# untitled.net
KiCad netlist of a schematic drawn in EAGLE
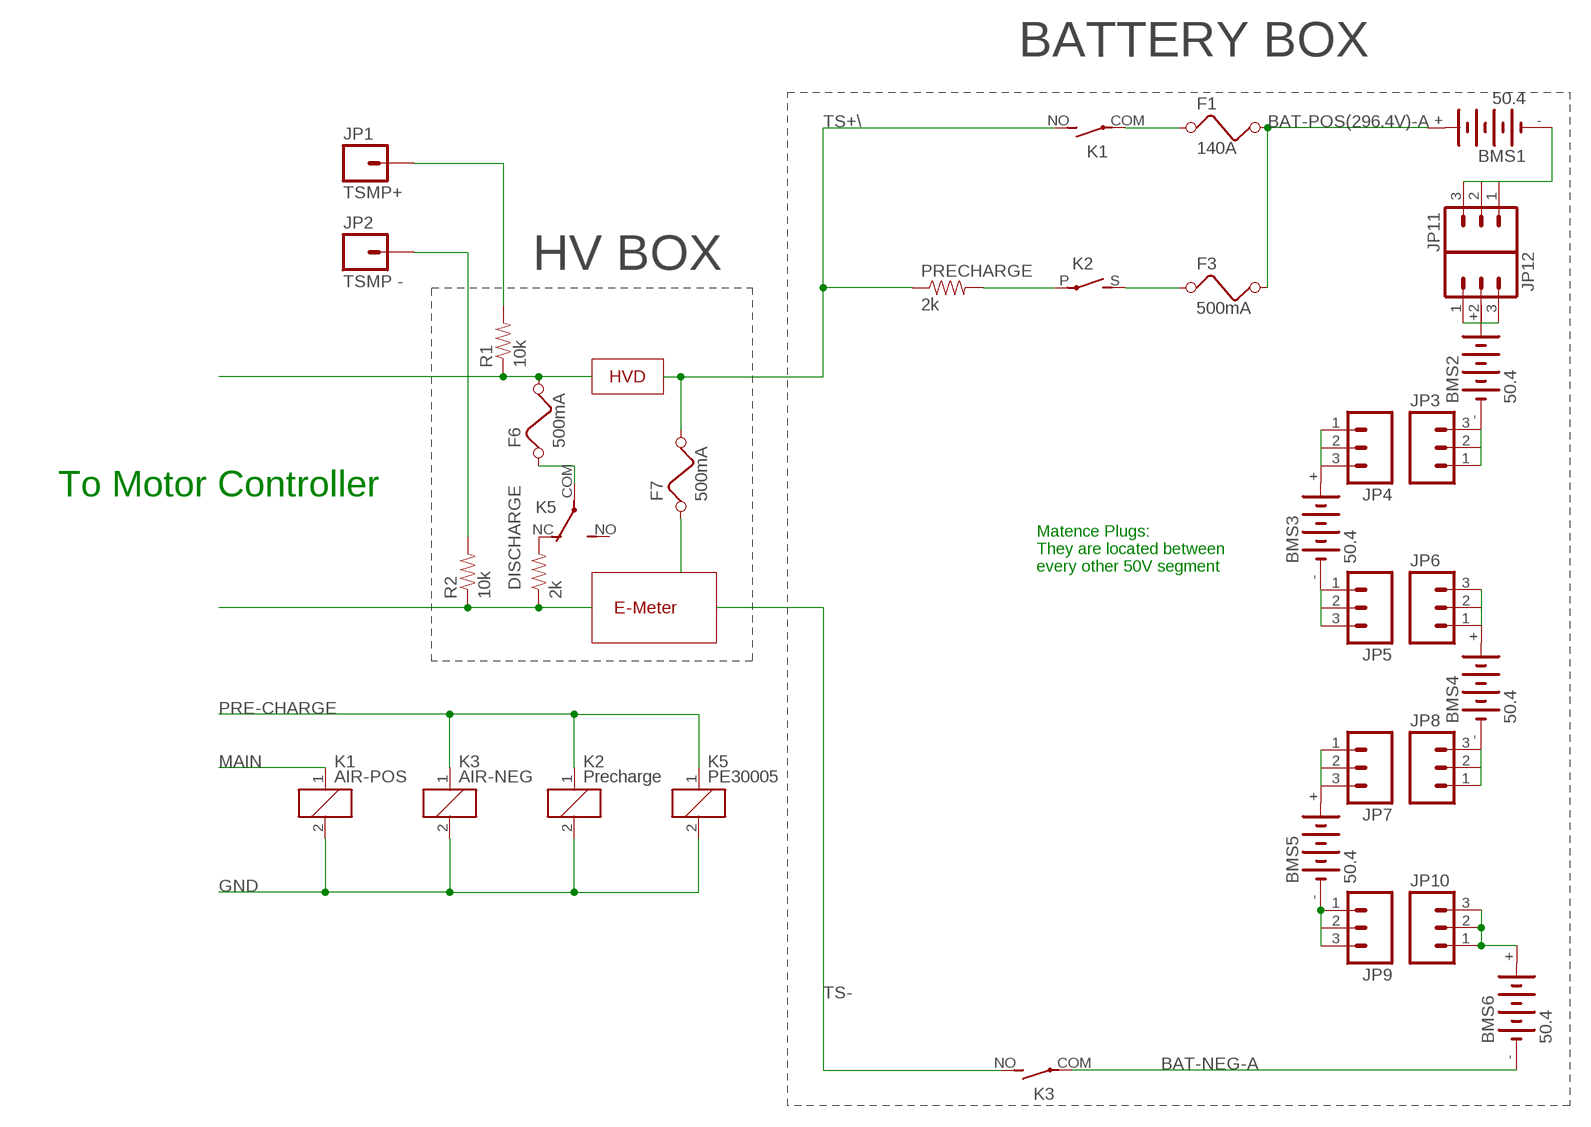
[diagram p0: schematic, sheet 1]
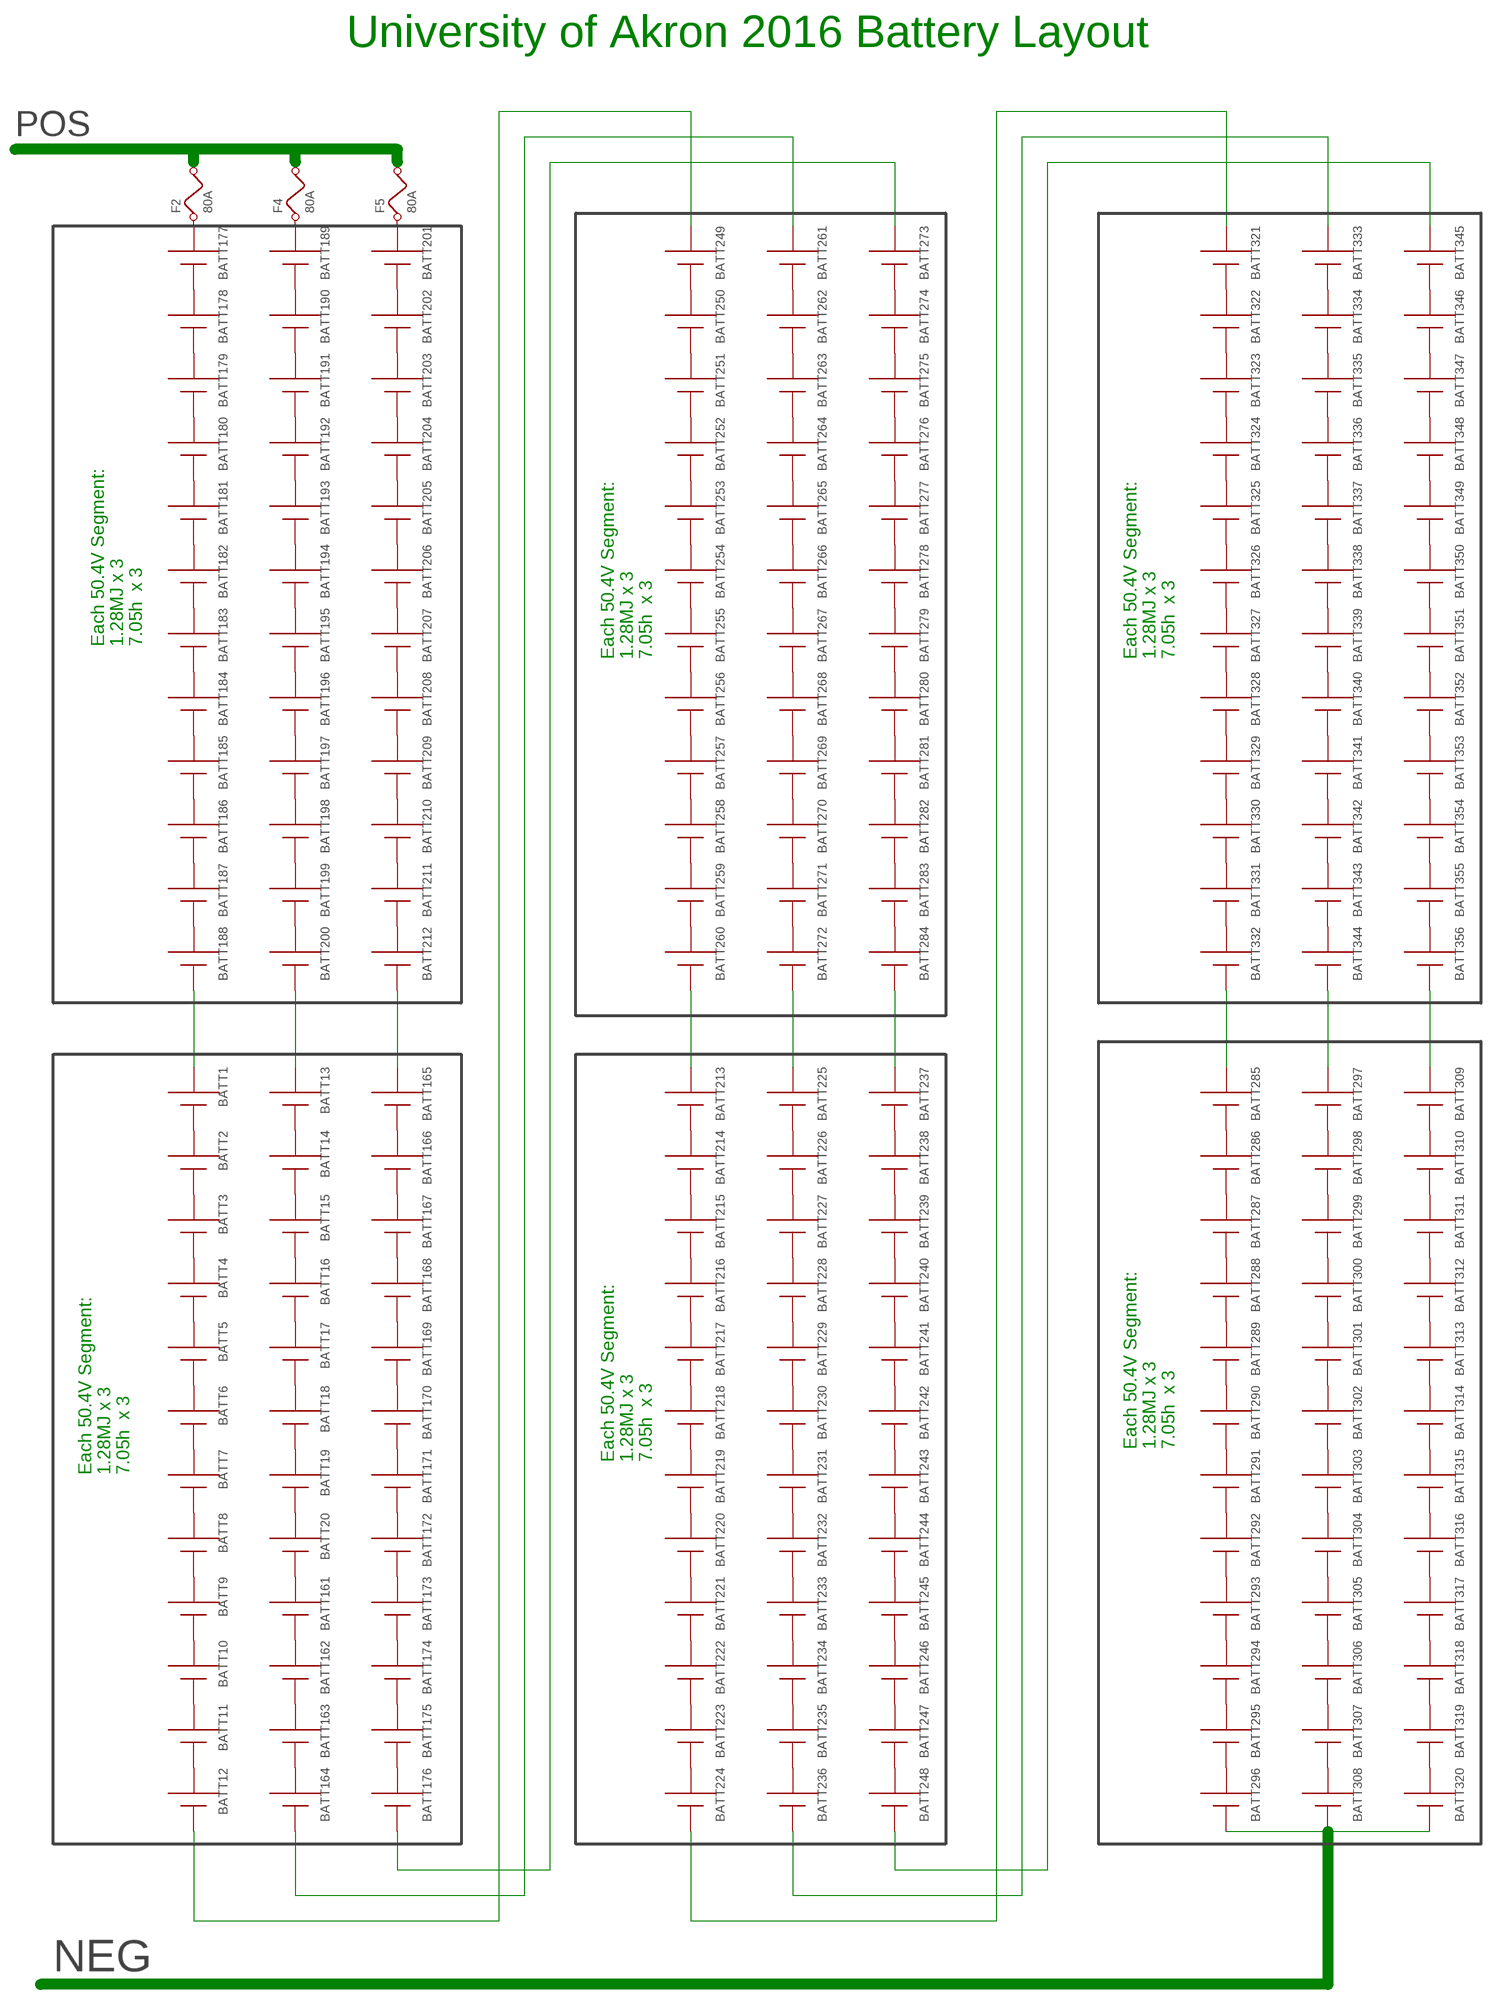
[diagram p1: schematic, sheet 2]

(export (version "E")
  (design (tool "Eeschema 10.0.6"))
  (components
    (comp (ref "BMS1")
      (value "50.4")
      (footprint "eagle-import:VST4")
      (libsource (lib "eagle-import") (part "VST4V8"))
    )
    (comp (ref "BMS2")
      (value "50.4")
      (footprint "eagle-import:VST4")
      (libsource (lib "eagle-import") (part "VST4V8"))
    )
    (comp (ref "BMS3")
      (value "50.4")
      (footprint "eagle-import:VST4")
      (libsource (lib "eagle-import") (part "VST4V8"))
    )
    (comp (ref "BMS4")
      (value "50.4")
      (footprint "eagle-import:VST4")
      (libsource (lib "eagle-import") (part "VST4V8"))
    )
    (comp (ref "BMS5")
      (value "50.4")
      (footprint "eagle-import:VST4")
      (libsource (lib "eagle-import") (part "VST4V8"))
    )
    (comp (ref "BMS6")
      (value "50.4")
      (footprint "eagle-import:VST4")
      (libsource (lib "eagle-import") (part "VST4V8"))
    )
    (comp (ref "DISCHARGE")
      (value "2k")
      (footprint "eagle-import:0603-RES")
      (libsource (lib "eagle-import") (part "2.0KOHM1/10W5%(0603)"))
    )
    (comp (ref "F1")
      (value "140A")
      (footprint "eagle-import:FUSE")
      (libsource (lib "eagle-import") (part "FUSE"))
    )
    (comp (ref "F3")
      (value "500mA")
      (footprint "eagle-import:FUSE")
      (libsource (lib "eagle-import") (part "FUSE"))
    )
    (comp (ref "F6")
      (value "500mA")
      (footprint "eagle-import:FUSE")
      (libsource (lib "eagle-import") (part "FUSE"))
    )
    (comp (ref "F7")
      (value "500mA")
      (footprint "eagle-import:FUSE")
      (libsource (lib "eagle-import") (part "FUSE"))
    )
    (comp (ref "JP1")
      (value "TSMP+")
      (footprint "eagle-import:SMTSO-256-ET")
      (libsource (lib "eagle-import") (part "M01-SMTSO-256-ET"))
    )
    (comp (ref "JP2")
      (value "TSMP -")
      (footprint "eagle-import:SMTSO-256-ET")
      (libsource (lib "eagle-import") (part "M01-SMTSO-256-ET"))
    )
    (comp (ref "JP3")
      (value "M03JST-PTH")
      (footprint "eagle-import:JST-3-PTH")
      (libsource (lib "eagle-import") (part "M03JST-PTH"))
    )
    (comp (ref "JP4")
      (value "M03JST-PTH")
      (footprint "eagle-import:JST-3-PTH")
      (libsource (lib "eagle-import") (part "M03JST-PTH"))
    )
    (comp (ref "JP5")
      (value "M03JST-PTH")
      (footprint "eagle-import:JST-3-PTH")
      (libsource (lib "eagle-import") (part "M03JST-PTH"))
    )
    (comp (ref "JP6")
      (value "M03JST-PTH")
      (footprint "eagle-import:JST-3-PTH")
      (libsource (lib "eagle-import") (part "M03JST-PTH"))
    )
    (comp (ref "JP7")
      (value "M03JST-PTH")
      (footprint "eagle-import:JST-3-PTH")
      (libsource (lib "eagle-import") (part "M03JST-PTH"))
    )
    (comp (ref "JP8")
      (value "M03JST-PTH")
      (footprint "eagle-import:JST-3-PTH")
      (libsource (lib "eagle-import") (part "M03JST-PTH"))
    )
    (comp (ref "JP9")
      (value "M03JST-PTH")
      (footprint "eagle-import:JST-3-PTH")
      (libsource (lib "eagle-import") (part "M03JST-PTH"))
    )
    (comp (ref "JP10")
      (value "M03JST-PTH")
      (footprint "eagle-import:JST-3-PTH")
      (libsource (lib "eagle-import") (part "M03JST-PTH"))
    )
    (comp (ref "JP11")
      (value "M03JST-PTH")
      (footprint "eagle-import:JST-3-PTH")
      (libsource (lib "eagle-import") (part "M03JST-PTH"))
    )
    (comp (ref "JP12")
      (value "M03JST-PTH")
      (footprint "eagle-import:JST-3-PTH")
      (libsource (lib "eagle-import") (part "M03JST-PTH"))
    )
    (comp (ref "K1")
      (value "AIR-POS")
      (footprint "eagle-import:APF30212A")
      (libsource (lib "eagle-import") (part "APF30212A"))
    )
    (comp (ref "K2")
      (value "Precharge")
      (footprint "eagle-import:G2RA")
      (libsource (lib "eagle-import") (part "G2RA"))
    )
    (comp (ref "K3")
      (value "AIR-NEG")
      (footprint "eagle-import:APF30212A")
      (libsource (lib "eagle-import") (part "APF30212A"))
    )
    (comp (ref "K5")
      (value "PE30005")
      (footprint "eagle-import:PE-FORM-C")
      (libsource (lib "eagle-import") (part "PE30?005"))
    )
    (comp (ref "PRECHARGE")
      (value "2k")
      (footprint "eagle-import:0603-RES")
      (libsource (lib "eagle-import") (part "2.0KOHM1/10W5%(0603)"))
    )
    (comp (ref "R1")
      (value "10k")
      (footprint "eagle-import:0805")
      (libsource (lib "eagle-import") (part "RESISTOR0805-RES"))
    )
    (comp (ref "R2")
      (value "10k")
      (footprint "eagle-import:0805")
      (libsource (lib "eagle-import") (part "RESISTOR0805-RES"))
    )
    (comp (ref "BATT1")
      (value "AAA")
      (footprint "eagle-import:12BH412")
      (libsource (lib "eagle-import") (part "AAA"))
    )
    (comp (ref "BATT2")
      (value "AAA")
      (footprint "eagle-import:12BH412")
      (libsource (lib "eagle-import") (part "AAA"))
    )
    (comp (ref "BATT3")
      (value "AAA")
      (footprint "eagle-import:12BH412")
      (libsource (lib "eagle-import") (part "AAA"))
    )
    (comp (ref "BATT4")
      (value "AAA")
      (footprint "eagle-import:12BH412")
      (libsource (lib "eagle-import") (part "AAA"))
    )
    (comp (ref "BATT5")
      (value "AAA")
      (footprint "eagle-import:12BH412")
      (libsource (lib "eagle-import") (part "AAA"))
    )
    (comp (ref "BATT6")
      (value "AAA")
      (footprint "eagle-import:12BH412")
      (libsource (lib "eagle-import") (part "AAA"))
    )
    (comp (ref "BATT7")
      (value "AAA")
      (footprint "eagle-import:12BH412")
      (libsource (lib "eagle-import") (part "AAA"))
    )
    (comp (ref "BATT8")
      (value "AAA")
      (footprint "eagle-import:12BH412")
      (libsource (lib "eagle-import") (part "AAA"))
    )
    (comp (ref "BATT9")
      (value "AAA")
      (footprint "eagle-import:12BH412")
      (libsource (lib "eagle-import") (part "AAA"))
    )
    (comp (ref "BATT10")
      (value "AAA")
      (footprint "eagle-import:12BH412")
      (libsource (lib "eagle-import") (part "AAA"))
    )
    (comp (ref "BATT11")
      (value "AAA")
      (footprint "eagle-import:12BH412")
      (libsource (lib "eagle-import") (part "AAA"))
    )
    (comp (ref "BATT12")
      (value "AAA")
      (footprint "eagle-import:12BH412")
      (libsource (lib "eagle-import") (part "AAA"))
    )
    (comp (ref "BATT13")
      (value "AAA")
      (footprint "eagle-import:12BH412")
      (libsource (lib "eagle-import") (part "AAA"))
    )
    (comp (ref "BATT14")
      (value "AAA")
      (footprint "eagle-import:12BH412")
      (libsource (lib "eagle-import") (part "AAA"))
    )
    (comp (ref "BATT15")
      (value "AAA")
      (footprint "eagle-import:12BH412")
      (libsource (lib "eagle-import") (part "AAA"))
    )
    (comp (ref "BATT16")
      (value "AAA")
      (footprint "eagle-import:12BH412")
      (libsource (lib "eagle-import") (part "AAA"))
    )
    (comp (ref "BATT17")
      (value "AAA")
      (footprint "eagle-import:12BH412")
      (libsource (lib "eagle-import") (part "AAA"))
    )
    (comp (ref "BATT18")
      (value "AAA")
      (footprint "eagle-import:12BH412")
      (libsource (lib "eagle-import") (part "AAA"))
    )
    (comp (ref "BATT19")
      (value "AAA")
      (footprint "eagle-import:12BH412")
      (libsource (lib "eagle-import") (part "AAA"))
    )
    (comp (ref "BATT20")
      (value "AAA")
      (footprint "eagle-import:12BH412")
      (libsource (lib "eagle-import") (part "AAA"))
    )
    (comp (ref "BATT161")
      (value "AAA")
      (footprint "eagle-import:12BH412")
      (libsource (lib "eagle-import") (part "AAA"))
    )
    (comp (ref "BATT162")
      (value "AAA")
      (footprint "eagle-import:12BH412")
      (libsource (lib "eagle-import") (part "AAA"))
    )
    (comp (ref "BATT163")
      (value "AAA")
      (footprint "eagle-import:12BH412")
      (libsource (lib "eagle-import") (part "AAA"))
    )
    (comp (ref "BATT164")
      (value "AAA")
      (footprint "eagle-import:12BH412")
      (libsource (lib "eagle-import") (part "AAA"))
    )
    (comp (ref "BATT165")
      (value "AAA")
      (footprint "eagle-import:12BH412")
      (libsource (lib "eagle-import") (part "AAA"))
    )
    (comp (ref "BATT166")
      (value "AAA")
      (footprint "eagle-import:12BH412")
      (libsource (lib "eagle-import") (part "AAA"))
    )
    (comp (ref "BATT167")
      (value "AAA")
      (footprint "eagle-import:12BH412")
      (libsource (lib "eagle-import") (part "AAA"))
    )
    (comp (ref "BATT168")
      (value "AAA")
      (footprint "eagle-import:12BH412")
      (libsource (lib "eagle-import") (part "AAA"))
    )
    (comp (ref "BATT169")
      (value "AAA")
      (footprint "eagle-import:12BH412")
      (libsource (lib "eagle-import") (part "AAA"))
    )
    (comp (ref "BATT170")
      (value "AAA")
      (footprint "eagle-import:12BH412")
      (libsource (lib "eagle-import") (part "AAA"))
    )
    (comp (ref "BATT171")
      (value "AAA")
      (footprint "eagle-import:12BH412")
      (libsource (lib "eagle-import") (part "AAA"))
    )
    (comp (ref "BATT172")
      (value "AAA")
      (footprint "eagle-import:12BH412")
      (libsource (lib "eagle-import") (part "AAA"))
    )
    (comp (ref "BATT173")
      (value "AAA")
      (footprint "eagle-import:12BH412")
      (libsource (lib "eagle-import") (part "AAA"))
    )
    (comp (ref "BATT174")
      (value "AAA")
      (footprint "eagle-import:12BH412")
      (libsource (lib "eagle-import") (part "AAA"))
    )
    (comp (ref "BATT175")
      (value "AAA")
      (footprint "eagle-import:12BH412")
      (libsource (lib "eagle-import") (part "AAA"))
    )
    (comp (ref "BATT176")
      (value "AAA")
      (footprint "eagle-import:12BH412")
      (libsource (lib "eagle-import") (part "AAA"))
    )
    (comp (ref "BATT177")
      (value "AAA")
      (footprint "eagle-import:12BH412")
      (libsource (lib "eagle-import") (part "AAA"))
    )
    (comp (ref "BATT178")
      (value "AAA")
      (footprint "eagle-import:12BH412")
      (libsource (lib "eagle-import") (part "AAA"))
    )
    (comp (ref "BATT179")
      (value "AAA")
      (footprint "eagle-import:12BH412")
      (libsource (lib "eagle-import") (part "AAA"))
    )
    (comp (ref "BATT180")
      (value "AAA")
      (footprint "eagle-import:12BH412")
      (libsource (lib "eagle-import") (part "AAA"))
    )
    (comp (ref "BATT181")
      (value "AAA")
      (footprint "eagle-import:12BH412")
      (libsource (lib "eagle-import") (part "AAA"))
    )
    (comp (ref "BATT182")
      (value "AAA")
      (footprint "eagle-import:12BH412")
      (libsource (lib "eagle-import") (part "AAA"))
    )
    (comp (ref "BATT183")
      (value "AAA")
      (footprint "eagle-import:12BH412")
      (libsource (lib "eagle-import") (part "AAA"))
    )
    (comp (ref "BATT184")
      (value "AAA")
      (footprint "eagle-import:12BH412")
      (libsource (lib "eagle-import") (part "AAA"))
    )
    (comp (ref "BATT185")
      (value "AAA")
      (footprint "eagle-import:12BH412")
      (libsource (lib "eagle-import") (part "AAA"))
    )
    (comp (ref "BATT186")
      (value "AAA")
      (footprint "eagle-import:12BH412")
      (libsource (lib "eagle-import") (part "AAA"))
    )
    (comp (ref "BATT187")
      (value "AAA")
      (footprint "eagle-import:12BH412")
      (libsource (lib "eagle-import") (part "AAA"))
    )
    (comp (ref "BATT188")
      (value "AAA")
      (footprint "eagle-import:12BH412")
      (libsource (lib "eagle-import") (part "AAA"))
    )
    (comp (ref "BATT189")
      (value "AAA")
      (footprint "eagle-import:12BH412")
      (libsource (lib "eagle-import") (part "AAA"))
    )
    (comp (ref "BATT190")
      (value "AAA")
      (footprint "eagle-import:12BH412")
      (libsource (lib "eagle-import") (part "AAA"))
    )
    (comp (ref "BATT191")
      (value "AAA")
      (footprint "eagle-import:12BH412")
      (libsource (lib "eagle-import") (part "AAA"))
    )
    (comp (ref "BATT192")
      (value "AAA")
      (footprint "eagle-import:12BH412")
      (libsource (lib "eagle-import") (part "AAA"))
    )
    (comp (ref "BATT193")
      (value "AAA")
      (footprint "eagle-import:12BH412")
      (libsource (lib "eagle-import") (part "AAA"))
    )
    (comp (ref "BATT194")
      (value "AAA")
      (footprint "eagle-import:12BH412")
      (libsource (lib "eagle-import") (part "AAA"))
    )
    (comp (ref "BATT195")
      (value "AAA")
      (footprint "eagle-import:12BH412")
      (libsource (lib "eagle-import") (part "AAA"))
    )
    (comp (ref "BATT196")
      (value "AAA")
      (footprint "eagle-import:12BH412")
      (libsource (lib "eagle-import") (part "AAA"))
    )
    (comp (ref "BATT197")
      (value "AAA")
      (footprint "eagle-import:12BH412")
      (libsource (lib "eagle-import") (part "AAA"))
    )
    (comp (ref "BATT198")
      (value "AAA")
      (footprint "eagle-import:12BH412")
      (libsource (lib "eagle-import") (part "AAA"))
    )
    (comp (ref "BATT199")
      (value "AAA")
      (footprint "eagle-import:12BH412")
      (libsource (lib "eagle-import") (part "AAA"))
    )
    (comp (ref "BATT200")
      (value "AAA")
      (footprint "eagle-import:12BH412")
      (libsource (lib "eagle-import") (part "AAA"))
    )
    (comp (ref "BATT201")
      (value "AAA")
      (footprint "eagle-import:12BH412")
      (libsource (lib "eagle-import") (part "AAA"))
    )
    (comp (ref "BATT202")
      (value "AAA")
      (footprint "eagle-import:12BH412")
      (libsource (lib "eagle-import") (part "AAA"))
    )
    (comp (ref "BATT203")
      (value "AAA")
      (footprint "eagle-import:12BH412")
      (libsource (lib "eagle-import") (part "AAA"))
    )
    (comp (ref "BATT204")
      (value "AAA")
      (footprint "eagle-import:12BH412")
      (libsource (lib "eagle-import") (part "AAA"))
    )
    (comp (ref "BATT205")
      (value "AAA")
      (footprint "eagle-import:12BH412")
      (libsource (lib "eagle-import") (part "AAA"))
    )
    (comp (ref "BATT206")
      (value "AAA")
      (footprint "eagle-import:12BH412")
      (libsource (lib "eagle-import") (part "AAA"))
    )
    (comp (ref "BATT207")
      (value "AAA")
      (footprint "eagle-import:12BH412")
      (libsource (lib "eagle-import") (part "AAA"))
    )
    (comp (ref "BATT208")
      (value "AAA")
      (footprint "eagle-import:12BH412")
      (libsource (lib "eagle-import") (part "AAA"))
    )
    (comp (ref "BATT209")
      (value "AAA")
      (footprint "eagle-import:12BH412")
      (libsource (lib "eagle-import") (part "AAA"))
    )
    (comp (ref "BATT210")
      (value "AAA")
      (footprint "eagle-import:12BH412")
      (libsource (lib "eagle-import") (part "AAA"))
    )
    (comp (ref "BATT211")
      (value "AAA")
      (footprint "eagle-import:12BH412")
      (libsource (lib "eagle-import") (part "AAA"))
    )
    (comp (ref "BATT212")
      (value "AAA")
      (footprint "eagle-import:12BH412")
      (libsource (lib "eagle-import") (part "AAA"))
    )
    (comp (ref "BATT213")
      (value "AAA")
      (footprint "eagle-import:12BH412")
      (libsource (lib "eagle-import") (part "AAA"))
    )
    (comp (ref "BATT214")
      (value "AAA")
      (footprint "eagle-import:12BH412")
      (libsource (lib "eagle-import") (part "AAA"))
    )
    (comp (ref "BATT215")
      (value "AAA")
      (footprint "eagle-import:12BH412")
      (libsource (lib "eagle-import") (part "AAA"))
    )
    (comp (ref "BATT216")
      (value "AAA")
      (footprint "eagle-import:12BH412")
      (libsource (lib "eagle-import") (part "AAA"))
    )
    (comp (ref "BATT217")
      (value "AAA")
      (footprint "eagle-import:12BH412")
      (libsource (lib "eagle-import") (part "AAA"))
    )
    (comp (ref "BATT218")
      (value "AAA")
      (footprint "eagle-import:12BH412")
      (libsource (lib "eagle-import") (part "AAA"))
    )
    (comp (ref "BATT219")
      (value "AAA")
      (footprint "eagle-import:12BH412")
      (libsource (lib "eagle-import") (part "AAA"))
    )
    (comp (ref "BATT220")
      (value "AAA")
      (footprint "eagle-import:12BH412")
      (libsource (lib "eagle-import") (part "AAA"))
    )
    (comp (ref "BATT221")
      (value "AAA")
      (footprint "eagle-import:12BH412")
      (libsource (lib "eagle-import") (part "AAA"))
    )
    (comp (ref "BATT222")
      (value "AAA")
      (footprint "eagle-import:12BH412")
      (libsource (lib "eagle-import") (part "AAA"))
    )
    (comp (ref "BATT223")
      (value "AAA")
      (footprint "eagle-import:12BH412")
      (libsource (lib "eagle-import") (part "AAA"))
    )
    (comp (ref "BATT224")
      (value "AAA")
      (footprint "eagle-import:12BH412")
      (libsource (lib "eagle-import") (part "AAA"))
    )
    (comp (ref "BATT225")
      (value "AAA")
      (footprint "eagle-import:12BH412")
      (libsource (lib "eagle-import") (part "AAA"))
    )
    (comp (ref "BATT226")
      (value "AAA")
      (footprint "eagle-import:12BH412")
      (libsource (lib "eagle-import") (part "AAA"))
    )
    (comp (ref "BATT227")
      (value "AAA")
      (footprint "eagle-import:12BH412")
      (libsource (lib "eagle-import") (part "AAA"))
    )
    (comp (ref "BATT228")
      (value "AAA")
      (footprint "eagle-import:12BH412")
      (libsource (lib "eagle-import") (part "AAA"))
    )
    (comp (ref "BATT229")
      (value "AAA")
      (footprint "eagle-import:12BH412")
      (libsource (lib "eagle-import") (part "AAA"))
    )
    (comp (ref "BATT230")
      (value "AAA")
      (footprint "eagle-import:12BH412")
      (libsource (lib "eagle-import") (part "AAA"))
    )
    (comp (ref "BATT231")
      (value "AAA")
      (footprint "eagle-import:12BH412")
      (libsource (lib "eagle-import") (part "AAA"))
    )
    (comp (ref "BATT232")
      (value "AAA")
      (footprint "eagle-import:12BH412")
      (libsource (lib "eagle-import") (part "AAA"))
    )
    (comp (ref "BATT233")
      (value "AAA")
      (footprint "eagle-import:12BH412")
      (libsource (lib "eagle-import") (part "AAA"))
    )
    (comp (ref "BATT234")
      (value "AAA")
      (footprint "eagle-import:12BH412")
      (libsource (lib "eagle-import") (part "AAA"))
    )
    (comp (ref "BATT235")
      (value "AAA")
      (footprint "eagle-import:12BH412")
      (libsource (lib "eagle-import") (part "AAA"))
    )
    (comp (ref "BATT236")
      (value "AAA")
      (footprint "eagle-import:12BH412")
      (libsource (lib "eagle-import") (part "AAA"))
    )
    (comp (ref "BATT237")
      (value "AAA")
      (footprint "eagle-import:12BH412")
      (libsource (lib "eagle-import") (part "AAA"))
    )
    (comp (ref "BATT238")
      (value "AAA")
      (footprint "eagle-import:12BH412")
      (libsource (lib "eagle-import") (part "AAA"))
    )
    (comp (ref "BATT239")
      (value "AAA")
      (footprint "eagle-import:12BH412")
      (libsource (lib "eagle-import") (part "AAA"))
    )
    (comp (ref "BATT240")
      (value "AAA")
      (footprint "eagle-import:12BH412")
      (libsource (lib "eagle-import") (part "AAA"))
    )
    (comp (ref "BATT241")
      (value "AAA")
      (footprint "eagle-import:12BH412")
      (libsource (lib "eagle-import") (part "AAA"))
    )
    (comp (ref "BATT242")
      (value "AAA")
      (footprint "eagle-import:12BH412")
      (libsource (lib "eagle-import") (part "AAA"))
    )
    (comp (ref "BATT243")
      (value "AAA")
      (footprint "eagle-import:12BH412")
      (libsource (lib "eagle-import") (part "AAA"))
    )
    (comp (ref "BATT244")
      (value "AAA")
      (footprint "eagle-import:12BH412")
      (libsource (lib "eagle-import") (part "AAA"))
    )
    (comp (ref "BATT245")
      (value "AAA")
      (footprint "eagle-import:12BH412")
      (libsource (lib "eagle-import") (part "AAA"))
    )
    (comp (ref "BATT246")
      (value "AAA")
      (footprint "eagle-import:12BH412")
      (libsource (lib "eagle-import") (part "AAA"))
    )
    (comp (ref "BATT247")
      (value "AAA")
      (footprint "eagle-import:12BH412")
      (libsource (lib "eagle-import") (part "AAA"))
    )
    (comp (ref "BATT248")
      (value "AAA")
      (footprint "eagle-import:12BH412")
      (libsource (lib "eagle-import") (part "AAA"))
    )
    (comp (ref "BATT249")
      (value "AAA")
      (footprint "eagle-import:12BH412")
      (libsource (lib "eagle-import") (part "AAA"))
    )
    (comp (ref "BATT250")
      (value "AAA")
      (footprint "eagle-import:12BH412")
      (libsource (lib "eagle-import") (part "AAA"))
    )
    (comp (ref "BATT251")
      (value "AAA")
      (footprint "eagle-import:12BH412")
      (libsource (lib "eagle-import") (part "AAA"))
    )
    (comp (ref "BATT252")
      (value "AAA")
      (footprint "eagle-import:12BH412")
      (libsource (lib "eagle-import") (part "AAA"))
    )
    (comp (ref "BATT253")
      (value "AAA")
      (footprint "eagle-import:12BH412")
      (libsource (lib "eagle-import") (part "AAA"))
    )
    (comp (ref "BATT254")
      (value "AAA")
      (footprint "eagle-import:12BH412")
      (libsource (lib "eagle-import") (part "AAA"))
    )
    (comp (ref "BATT255")
      (value "AAA")
      (footprint "eagle-import:12BH412")
      (libsource (lib "eagle-import") (part "AAA"))
    )
    (comp (ref "BATT256")
      (value "AAA")
      (footprint "eagle-import:12BH412")
      (libsource (lib "eagle-import") (part "AAA"))
    )
    (comp (ref "BATT257")
      (value "AAA")
      (footprint "eagle-import:12BH412")
      (libsource (lib "eagle-import") (part "AAA"))
    )
    (comp (ref "BATT258")
      (value "AAA")
      (footprint "eagle-import:12BH412")
      (libsource (lib "eagle-import") (part "AAA"))
    )
    (comp (ref "BATT259")
      (value "AAA")
      (footprint "eagle-import:12BH412")
      (libsource (lib "eagle-import") (part "AAA"))
    )
    (comp (ref "BATT260")
      (value "AAA")
      (footprint "eagle-import:12BH412")
      (libsource (lib "eagle-import") (part "AAA"))
    )
    (comp (ref "BATT261")
      (value "AAA")
      (footprint "eagle-import:12BH412")
      (libsource (lib "eagle-import") (part "AAA"))
    )
    (comp (ref "BATT262")
      (value "AAA")
      (footprint "eagle-import:12BH412")
      (libsource (lib "eagle-import") (part "AAA"))
    )
    (comp (ref "BATT263")
      (value "AAA")
      (footprint "eagle-import:12BH412")
      (libsource (lib "eagle-import") (part "AAA"))
    )
    (comp (ref "BATT264")
      (value "AAA")
      (footprint "eagle-import:12BH412")
      (libsource (lib "eagle-import") (part "AAA"))
    )
    (comp (ref "BATT265")
      (value "AAA")
      (footprint "eagle-import:12BH412")
      (libsource (lib "eagle-import") (part "AAA"))
    )
    (comp (ref "BATT266")
      (value "AAA")
      (footprint "eagle-import:12BH412")
      (libsource (lib "eagle-import") (part "AAA"))
    )
    (comp (ref "BATT267")
      (value "AAA")
      (footprint "eagle-import:12BH412")
      (libsource (lib "eagle-import") (part "AAA"))
    )
    (comp (ref "BATT268")
      (value "AAA")
      (footprint "eagle-import:12BH412")
      (libsource (lib "eagle-import") (part "AAA"))
    )
    (comp (ref "BATT269")
      (value "AAA")
      (footprint "eagle-import:12BH412")
      (libsource (lib "eagle-import") (part "AAA"))
    )
    (comp (ref "BATT270")
      (value "AAA")
      (footprint "eagle-import:12BH412")
      (libsource (lib "eagle-import") (part "AAA"))
    )
    (comp (ref "BATT271")
      (value "AAA")
      (footprint "eagle-import:12BH412")
      (libsource (lib "eagle-import") (part "AAA"))
    )
    (comp (ref "BATT272")
      (value "AAA")
      (footprint "eagle-import:12BH412")
      (libsource (lib "eagle-import") (part "AAA"))
    )
    (comp (ref "BATT273")
      (value "AAA")
      (footprint "eagle-import:12BH412")
      (libsource (lib "eagle-import") (part "AAA"))
    )
    (comp (ref "BATT274")
      (value "AAA")
      (footprint "eagle-import:12BH412")
      (libsource (lib "eagle-import") (part "AAA"))
    )
    (comp (ref "BATT275")
      (value "AAA")
      (footprint "eagle-import:12BH412")
      (libsource (lib "eagle-import") (part "AAA"))
    )
    (comp (ref "BATT276")
      (value "AAA")
      (footprint "eagle-import:12BH412")
      (libsource (lib "eagle-import") (part "AAA"))
    )
    (comp (ref "BATT277")
      (value "AAA")
      (footprint "eagle-import:12BH412")
      (libsource (lib "eagle-import") (part "AAA"))
    )
    (comp (ref "BATT278")
      (value "AAA")
      (footprint "eagle-import:12BH412")
      (libsource (lib "eagle-import") (part "AAA"))
    )
    (comp (ref "BATT279")
      (value "AAA")
      (footprint "eagle-import:12BH412")
      (libsource (lib "eagle-import") (part "AAA"))
    )
    (comp (ref "BATT280")
      (value "AAA")
      (footprint "eagle-import:12BH412")
      (libsource (lib "eagle-import") (part "AAA"))
    )
    (comp (ref "BATT281")
      (value "AAA")
      (footprint "eagle-import:12BH412")
      (libsource (lib "eagle-import") (part "AAA"))
    )
    (comp (ref "BATT282")
      (value "AAA")
      (footprint "eagle-import:12BH412")
      (libsource (lib "eagle-import") (part "AAA"))
    )
    (comp (ref "BATT283")
      (value "AAA")
      (footprint "eagle-import:12BH412")
      (libsource (lib "eagle-import") (part "AAA"))
    )
    (comp (ref "BATT284")
      (value "AAA")
      (footprint "eagle-import:12BH412")
      (libsource (lib "eagle-import") (part "AAA"))
    )
    (comp (ref "BATT285")
      (value "AAA")
      (footprint "eagle-import:12BH412")
      (libsource (lib "eagle-import") (part "AAA"))
    )
    (comp (ref "BATT286")
      (value "AAA")
      (footprint "eagle-import:12BH412")
      (libsource (lib "eagle-import") (part "AAA"))
    )
    (comp (ref "BATT287")
      (value "AAA")
      (footprint "eagle-import:12BH412")
      (libsource (lib "eagle-import") (part "AAA"))
    )
    (comp (ref "BATT288")
      (value "AAA")
      (footprint "eagle-import:12BH412")
      (libsource (lib "eagle-import") (part "AAA"))
    )
    (comp (ref "BATT289")
      (value "AAA")
      (footprint "eagle-import:12BH412")
      (libsource (lib "eagle-import") (part "AAA"))
    )
    (comp (ref "BATT290")
      (value "AAA")
      (footprint "eagle-import:12BH412")
      (libsource (lib "eagle-import") (part "AAA"))
    )
    (comp (ref "BATT291")
      (value "AAA")
      (footprint "eagle-import:12BH412")
      (libsource (lib "eagle-import") (part "AAA"))
    )
    (comp (ref "BATT292")
      (value "AAA")
      (footprint "eagle-import:12BH412")
      (libsource (lib "eagle-import") (part "AAA"))
    )
    (comp (ref "BATT293")
      (value "AAA")
      (footprint "eagle-import:12BH412")
      (libsource (lib "eagle-import") (part "AAA"))
    )
    (comp (ref "BATT294")
      (value "AAA")
      (footprint "eagle-import:12BH412")
      (libsource (lib "eagle-import") (part "AAA"))
    )
    (comp (ref "BATT295")
      (value "AAA")
      (footprint "eagle-import:12BH412")
      (libsource (lib "eagle-import") (part "AAA"))
    )
    (comp (ref "BATT296")
      (value "AAA")
      (footprint "eagle-import:12BH412")
      (libsource (lib "eagle-import") (part "AAA"))
    )
    (comp (ref "BATT297")
      (value "AAA")
      (footprint "eagle-import:12BH412")
      (libsource (lib "eagle-import") (part "AAA"))
    )
    (comp (ref "BATT298")
      (value "AAA")
      (footprint "eagle-import:12BH412")
      (libsource (lib "eagle-import") (part "AAA"))
    )
    (comp (ref "BATT299")
      (value "AAA")
      (footprint "eagle-import:12BH412")
      (libsource (lib "eagle-import") (part "AAA"))
    )
    (comp (ref "BATT300")
      (value "AAA")
      (footprint "eagle-import:12BH412")
      (libsource (lib "eagle-import") (part "AAA"))
    )
    (comp (ref "BATT301")
      (value "AAA")
      (footprint "eagle-import:12BH412")
      (libsource (lib "eagle-import") (part "AAA"))
    )
    (comp (ref "BATT302")
      (value "AAA")
      (footprint "eagle-import:12BH412")
      (libsource (lib "eagle-import") (part "AAA"))
    )
    (comp (ref "BATT303")
      (value "AAA")
      (footprint "eagle-import:12BH412")
      (libsource (lib "eagle-import") (part "AAA"))
    )
    (comp (ref "BATT304")
      (value "AAA")
      (footprint "eagle-import:12BH412")
      (libsource (lib "eagle-import") (part "AAA"))
    )
    (comp (ref "BATT305")
      (value "AAA")
      (footprint "eagle-import:12BH412")
      (libsource (lib "eagle-import") (part "AAA"))
    )
    (comp (ref "BATT306")
      (value "AAA")
      (footprint "eagle-import:12BH412")
      (libsource (lib "eagle-import") (part "AAA"))
    )
    (comp (ref "BATT307")
      (value "AAA")
      (footprint "eagle-import:12BH412")
      (libsource (lib "eagle-import") (part "AAA"))
    )
    (comp (ref "BATT308")
      (value "AAA")
      (footprint "eagle-import:12BH412")
      (libsource (lib "eagle-import") (part "AAA"))
    )
    (comp (ref "BATT309")
      (value "AAA")
      (footprint "eagle-import:12BH412")
      (libsource (lib "eagle-import") (part "AAA"))
    )
    (comp (ref "BATT310")
      (value "AAA")
      (footprint "eagle-import:12BH412")
      (libsource (lib "eagle-import") (part "AAA"))
    )
    (comp (ref "BATT311")
      (value "AAA")
      (footprint "eagle-import:12BH412")
      (libsource (lib "eagle-import") (part "AAA"))
    )
    (comp (ref "BATT312")
      (value "AAA")
      (footprint "eagle-import:12BH412")
      (libsource (lib "eagle-import") (part "AAA"))
    )
    (comp (ref "BATT313")
      (value "AAA")
      (footprint "eagle-import:12BH412")
      (libsource (lib "eagle-import") (part "AAA"))
    )
    (comp (ref "BATT314")
      (value "AAA")
      (footprint "eagle-import:12BH412")
      (libsource (lib "eagle-import") (part "AAA"))
    )
    (comp (ref "BATT315")
      (value "AAA")
      (footprint "eagle-import:12BH412")
      (libsource (lib "eagle-import") (part "AAA"))
    )
    (comp (ref "BATT316")
      (value "AAA")
      (footprint "eagle-import:12BH412")
      (libsource (lib "eagle-import") (part "AAA"))
    )
    (comp (ref "BATT317")
      (value "AAA")
      (footprint "eagle-import:12BH412")
      (libsource (lib "eagle-import") (part "AAA"))
    )
    (comp (ref "BATT318")
      (value "AAA")
      (footprint "eagle-import:12BH412")
      (libsource (lib "eagle-import") (part "AAA"))
    )
    (comp (ref "BATT319")
      (value "AAA")
      (footprint "eagle-import:12BH412")
      (libsource (lib "eagle-import") (part "AAA"))
    )
    (comp (ref "BATT320")
      (value "AAA")
      (footprint "eagle-import:12BH412")
      (libsource (lib "eagle-import") (part "AAA"))
    )
    (comp (ref "BATT321")
      (value "AAA")
      (footprint "eagle-import:12BH412")
      (libsource (lib "eagle-import") (part "AAA"))
    )
    (comp (ref "BATT322")
      (value "AAA")
      (footprint "eagle-import:12BH412")
      (libsource (lib "eagle-import") (part "AAA"))
    )
    (comp (ref "BATT323")
      (value "AAA")
      (footprint "eagle-import:12BH412")
      (libsource (lib "eagle-import") (part "AAA"))
    )
    (comp (ref "BATT324")
      (value "AAA")
      (footprint "eagle-import:12BH412")
      (libsource (lib "eagle-import") (part "AAA"))
    )
    (comp (ref "BATT325")
      (value "AAA")
      (footprint "eagle-import:12BH412")
      (libsource (lib "eagle-import") (part "AAA"))
    )
    (comp (ref "BATT326")
      (value "AAA")
      (footprint "eagle-import:12BH412")
      (libsource (lib "eagle-import") (part "AAA"))
    )
    (comp (ref "BATT327")
      (value "AAA")
      (footprint "eagle-import:12BH412")
      (libsource (lib "eagle-import") (part "AAA"))
    )
    (comp (ref "BATT328")
      (value "AAA")
      (footprint "eagle-import:12BH412")
      (libsource (lib "eagle-import") (part "AAA"))
    )
    (comp (ref "BATT329")
      (value "AAA")
      (footprint "eagle-import:12BH412")
      (libsource (lib "eagle-import") (part "AAA"))
    )
    (comp (ref "BATT330")
      (value "AAA")
      (footprint "eagle-import:12BH412")
      (libsource (lib "eagle-import") (part "AAA"))
    )
    (comp (ref "BATT331")
      (value "AAA")
      (footprint "eagle-import:12BH412")
      (libsource (lib "eagle-import") (part "AAA"))
    )
    (comp (ref "BATT332")
      (value "AAA")
      (footprint "eagle-import:12BH412")
      (libsource (lib "eagle-import") (part "AAA"))
    )
    (comp (ref "BATT333")
      (value "AAA")
      (footprint "eagle-import:12BH412")
      (libsource (lib "eagle-import") (part "AAA"))
    )
    (comp (ref "BATT334")
      (value "AAA")
      (footprint "eagle-import:12BH412")
      (libsource (lib "eagle-import") (part "AAA"))
    )
    (comp (ref "BATT335")
      (value "AAA")
      (footprint "eagle-import:12BH412")
      (libsource (lib "eagle-import") (part "AAA"))
    )
    (comp (ref "BATT336")
      (value "AAA")
      (footprint "eagle-import:12BH412")
      (libsource (lib "eagle-import") (part "AAA"))
    )
    (comp (ref "BATT337")
      (value "AAA")
      (footprint "eagle-import:12BH412")
      (libsource (lib "eagle-import") (part "AAA"))
    )
    (comp (ref "BATT338")
      (value "AAA")
      (footprint "eagle-import:12BH412")
      (libsource (lib "eagle-import") (part "AAA"))
    )
    (comp (ref "BATT339")
      (value "AAA")
      (footprint "eagle-import:12BH412")
      (libsource (lib "eagle-import") (part "AAA"))
    )
    (comp (ref "BATT340")
      (value "AAA")
      (footprint "eagle-import:12BH412")
      (libsource (lib "eagle-import") (part "AAA"))
    )
    (comp (ref "BATT341")
      (value "AAA")
      (footprint "eagle-import:12BH412")
      (libsource (lib "eagle-import") (part "AAA"))
    )
    (comp (ref "BATT342")
      (value "AAA")
      (footprint "eagle-import:12BH412")
      (libsource (lib "eagle-import") (part "AAA"))
    )
    (comp (ref "BATT343")
      (value "AAA")
      (footprint "eagle-import:12BH412")
      (libsource (lib "eagle-import") (part "AAA"))
    )
    (comp (ref "BATT344")
      (value "AAA")
      (footprint "eagle-import:12BH412")
      (libsource (lib "eagle-import") (part "AAA"))
    )
    (comp (ref "BATT345")
      (value "AAA")
      (footprint "eagle-import:12BH412")
      (libsource (lib "eagle-import") (part "AAA"))
    )
    (comp (ref "BATT346")
      (value "AAA")
      (footprint "eagle-import:12BH412")
      (libsource (lib "eagle-import") (part "AAA"))
    )
    (comp (ref "BATT347")
      (value "AAA")
      (footprint "eagle-import:12BH412")
      (libsource (lib "eagle-import") (part "AAA"))
    )
    (comp (ref "BATT348")
      (value "AAA")
      (footprint "eagle-import:12BH412")
      (libsource (lib "eagle-import") (part "AAA"))
    )
    (comp (ref "BATT349")
      (value "AAA")
      (footprint "eagle-import:12BH412")
      (libsource (lib "eagle-import") (part "AAA"))
    )
    (comp (ref "BATT350")
      (value "AAA")
      (footprint "eagle-import:12BH412")
      (libsource (lib "eagle-import") (part "AAA"))
    )
    (comp (ref "BATT351")
      (value "AAA")
      (footprint "eagle-import:12BH412")
      (libsource (lib "eagle-import") (part "AAA"))
    )
    (comp (ref "BATT352")
      (value "AAA")
      (footprint "eagle-import:12BH412")
      (libsource (lib "eagle-import") (part "AAA"))
    )
    (comp (ref "BATT353")
      (value "AAA")
      (footprint "eagle-import:12BH412")
      (libsource (lib "eagle-import") (part "AAA"))
    )
    (comp (ref "BATT354")
      (value "AAA")
      (footprint "eagle-import:12BH412")
      (libsource (lib "eagle-import") (part "AAA"))
    )
    (comp (ref "BATT355")
      (value "AAA")
      (footprint "eagle-import:12BH412")
      (libsource (lib "eagle-import") (part "AAA"))
    )
    (comp (ref "BATT356")
      (value "AAA")
      (footprint "eagle-import:12BH412")
      (libsource (lib "eagle-import") (part "AAA"))
    )
    (comp (ref "F2")
      (value "80A")
      (footprint "eagle-import:FUSE")
      (libsource (lib "eagle-import") (part "FUSE"))
    )
    (comp (ref "F4")
      (value "80A")
      (footprint "eagle-import:FUSE")
      (libsource (lib "eagle-import") (part "FUSE"))
    )
    (comp (ref "F5")
      (value "80A")
      (footprint "eagle-import:FUSE")
      (libsource (lib "eagle-import") (part "FUSE"))
    )
  )
  (nets
    (net (code "1") (name "BAT-NEG-A") (class "Default")
      (node (ref "BMS6") (pin "-") (pinfunction "-_-") (pintype "passive"))
      (node (ref "K3") (pin "COM") (pinfunction "P_COM") (pintype "passive"))
    )
    (net (code "2") (name "BAT-POS(296.4V)-A") (class "Default")
      (node (ref "BMS1") (pin "+") (pinfunction "+_+") (pintype "passive"))
      (node (ref "F1") (pin "2") (pinfunction "2_2") (pintype "passive"))
      (node (ref "F3") (pin "2") (pinfunction "2_2") (pintype "passive"))
    )
    (net (code "3") (name "GND") (class "Default")
      (node (ref "K1") (pin "2") (pinfunction "2_2") (pintype "passive"))
      (node (ref "K2") (pin "2") (pinfunction "2_2") (pintype "passive"))
      (node (ref "K3") (pin "2") (pinfunction "2_2") (pintype "passive"))
      (node (ref "K5") (pin "2") (pinfunction "2_2") (pintype "passive"))
    )
    (net (code "4") (name "MAIN") (class "Default")
      (node (ref "K1") (pin "1") (pinfunction "1_1") (pintype "passive"))
    )
    (net (code "5") (name "NEG") (class "Default")
      (node (ref "BATT296") (pin "+") (pinfunction "+_+") (pintype "bidirectional"))
      (node (ref "BATT308") (pin "+") (pinfunction "+_+") (pintype "bidirectional"))
      (node (ref "BATT320") (pin "+") (pinfunction "+_+") (pintype "bidirectional"))
    )
    (net (code "6") (name "Net-(BATT1-Pad+)") (class "Default")
      (node (ref "BATT1") (pin "+") (pinfunction "+_+") (pintype "bidirectional"))
      (node (ref "BATT2") (pin "-") (pinfunction "-_-") (pintype "bidirectional"))
    )
    (net (code "7") (name "Net-(BATT1-Pad-)") (class "Default")
      (node (ref "BATT1") (pin "-") (pinfunction "-_-") (pintype "bidirectional"))
      (node (ref "BATT188") (pin "+") (pinfunction "+_+") (pintype "bidirectional"))
    )
    (net (code "8") (name "Net-(BATT2-Pad+)") (class "Default")
      (node (ref "BATT2") (pin "+") (pinfunction "+_+") (pintype "bidirectional"))
      (node (ref "BATT3") (pin "-") (pinfunction "-_-") (pintype "bidirectional"))
    )
    (net (code "9") (name "Net-(BATT3-Pad+)") (class "Default")
      (node (ref "BATT3") (pin "+") (pinfunction "+_+") (pintype "bidirectional"))
      (node (ref "BATT4") (pin "-") (pinfunction "-_-") (pintype "bidirectional"))
    )
    (net (code "10") (name "Net-(BATT4-Pad+)") (class "Default")
      (node (ref "BATT4") (pin "+") (pinfunction "+_+") (pintype "bidirectional"))
      (node (ref "BATT5") (pin "-") (pinfunction "-_-") (pintype "bidirectional"))
    )
    (net (code "11") (name "Net-(BATT5-Pad+)") (class "Default")
      (node (ref "BATT5") (pin "+") (pinfunction "+_+") (pintype "bidirectional"))
      (node (ref "BATT6") (pin "-") (pinfunction "-_-") (pintype "bidirectional"))
    )
    (net (code "12") (name "Net-(BATT6-Pad+)") (class "Default")
      (node (ref "BATT6") (pin "+") (pinfunction "+_+") (pintype "bidirectional"))
      (node (ref "BATT7") (pin "-") (pinfunction "-_-") (pintype "bidirectional"))
    )
    (net (code "13") (name "Net-(BATT7-Pad+)") (class "Default")
      (node (ref "BATT7") (pin "+") (pinfunction "+_+") (pintype "bidirectional"))
      (node (ref "BATT8") (pin "-") (pinfunction "-_-") (pintype "bidirectional"))
    )
    (net (code "14") (name "Net-(BATT8-Pad+)") (class "Default")
      (node (ref "BATT8") (pin "+") (pinfunction "+_+") (pintype "bidirectional"))
      (node (ref "BATT9") (pin "-") (pinfunction "-_-") (pintype "bidirectional"))
    )
    (net (code "15") (name "Net-(BATT10-Pad+)") (class "Default")
      (node (ref "BATT10") (pin "+") (pinfunction "+_+") (pintype "bidirectional"))
      (node (ref "BATT11") (pin "-") (pinfunction "-_-") (pintype "bidirectional"))
    )
    (net (code "16") (name "Net-(BATT10-Pad-)") (class "Default")
      (node (ref "BATT10") (pin "-") (pinfunction "-_-") (pintype "bidirectional"))
      (node (ref "BATT9") (pin "+") (pinfunction "+_+") (pintype "bidirectional"))
    )
    (net (code "17") (name "Net-(BATT11-Pad+)") (class "Default")
      (node (ref "BATT11") (pin "+") (pinfunction "+_+") (pintype "bidirectional"))
      (node (ref "BATT12") (pin "-") (pinfunction "-_-") (pintype "bidirectional"))
    )
    (net (code "18") (name "Net-(BATT12-Pad+)") (class "Default")
      (node (ref "BATT12") (pin "+") (pinfunction "+_+") (pintype "bidirectional"))
      (node (ref "BATT249") (pin "-") (pinfunction "-_-") (pintype "bidirectional"))
    )
    (net (code "19") (name "Net-(BATT13-Pad+)") (class "Default")
      (node (ref "BATT13") (pin "+") (pinfunction "+_+") (pintype "bidirectional"))
      (node (ref "BATT14") (pin "-") (pinfunction "-_-") (pintype "bidirectional"))
    )
    (net (code "20") (name "Net-(BATT13-Pad-)") (class "Default")
      (node (ref "BATT13") (pin "-") (pinfunction "-_-") (pintype "bidirectional"))
      (node (ref "BATT200") (pin "+") (pinfunction "+_+") (pintype "bidirectional"))
    )
    (net (code "21") (name "Net-(BATT14-Pad+)") (class "Default")
      (node (ref "BATT14") (pin "+") (pinfunction "+_+") (pintype "bidirectional"))
      (node (ref "BATT15") (pin "-") (pinfunction "-_-") (pintype "bidirectional"))
    )
    (net (code "22") (name "Net-(BATT15-Pad+)") (class "Default")
      (node (ref "BATT15") (pin "+") (pinfunction "+_+") (pintype "bidirectional"))
      (node (ref "BATT16") (pin "-") (pinfunction "-_-") (pintype "bidirectional"))
    )
    (net (code "23") (name "Net-(BATT16-Pad+)") (class "Default")
      (node (ref "BATT16") (pin "+") (pinfunction "+_+") (pintype "bidirectional"))
      (node (ref "BATT17") (pin "-") (pinfunction "-_-") (pintype "bidirectional"))
    )
    (net (code "24") (name "Net-(BATT17-Pad+)") (class "Default")
      (node (ref "BATT17") (pin "+") (pinfunction "+_+") (pintype "bidirectional"))
      (node (ref "BATT18") (pin "-") (pinfunction "-_-") (pintype "bidirectional"))
    )
    (net (code "25") (name "Net-(BATT18-Pad+)") (class "Default")
      (node (ref "BATT18") (pin "+") (pinfunction "+_+") (pintype "bidirectional"))
      (node (ref "BATT19") (pin "-") (pinfunction "-_-") (pintype "bidirectional"))
    )
    (net (code "26") (name "Net-(BATT19-Pad+)") (class "Default")
      (node (ref "BATT19") (pin "+") (pinfunction "+_+") (pintype "bidirectional"))
      (node (ref "BATT20") (pin "-") (pinfunction "-_-") (pintype "bidirectional"))
    )
    (net (code "27") (name "Net-(BATT161-Pad+)") (class "Default")
      (node (ref "BATT161") (pin "+") (pinfunction "+_+") (pintype "bidirectional"))
      (node (ref "BATT162") (pin "-") (pinfunction "-_-") (pintype "bidirectional"))
    )
    (net (code "28") (name "Net-(BATT161-Pad-)") (class "Default")
      (node (ref "BATT161") (pin "-") (pinfunction "-_-") (pintype "bidirectional"))
      (node (ref "BATT20") (pin "+") (pinfunction "+_+") (pintype "bidirectional"))
    )
    (net (code "29") (name "Net-(BATT162-Pad+)") (class "Default")
      (node (ref "BATT162") (pin "+") (pinfunction "+_+") (pintype "bidirectional"))
      (node (ref "BATT163") (pin "-") (pinfunction "-_-") (pintype "bidirectional"))
    )
    (net (code "30") (name "Net-(BATT163-Pad+)") (class "Default")
      (node (ref "BATT163") (pin "+") (pinfunction "+_+") (pintype "bidirectional"))
      (node (ref "BATT164") (pin "-") (pinfunction "-_-") (pintype "bidirectional"))
    )
    (net (code "31") (name "Net-(BATT164-Pad+)") (class "Default")
      (node (ref "BATT164") (pin "+") (pinfunction "+_+") (pintype "bidirectional"))
      (node (ref "BATT261") (pin "-") (pinfunction "-_-") (pintype "bidirectional"))
    )
    (net (code "32") (name "Net-(BATT165-Pad+)") (class "Default")
      (node (ref "BATT165") (pin "+") (pinfunction "+_+") (pintype "bidirectional"))
      (node (ref "BATT166") (pin "-") (pinfunction "-_-") (pintype "bidirectional"))
    )
    (net (code "33") (name "Net-(BATT165-Pad-)") (class "Default")
      (node (ref "BATT165") (pin "-") (pinfunction "-_-") (pintype "bidirectional"))
      (node (ref "BATT212") (pin "+") (pinfunction "+_+") (pintype "bidirectional"))
    )
    (net (code "34") (name "Net-(BATT166-Pad+)") (class "Default")
      (node (ref "BATT166") (pin "+") (pinfunction "+_+") (pintype "bidirectional"))
      (node (ref "BATT167") (pin "-") (pinfunction "-_-") (pintype "bidirectional"))
    )
    (net (code "35") (name "Net-(BATT167-Pad+)") (class "Default")
      (node (ref "BATT167") (pin "+") (pinfunction "+_+") (pintype "bidirectional"))
      (node (ref "BATT168") (pin "-") (pinfunction "-_-") (pintype "bidirectional"))
    )
    (net (code "36") (name "Net-(BATT168-Pad+)") (class "Default")
      (node (ref "BATT168") (pin "+") (pinfunction "+_+") (pintype "bidirectional"))
      (node (ref "BATT169") (pin "-") (pinfunction "-_-") (pintype "bidirectional"))
    )
    (net (code "37") (name "Net-(BATT169-Pad+)") (class "Default")
      (node (ref "BATT169") (pin "+") (pinfunction "+_+") (pintype "bidirectional"))
      (node (ref "BATT170") (pin "-") (pinfunction "-_-") (pintype "bidirectional"))
    )
    (net (code "38") (name "Net-(BATT170-Pad+)") (class "Default")
      (node (ref "BATT170") (pin "+") (pinfunction "+_+") (pintype "bidirectional"))
      (node (ref "BATT171") (pin "-") (pinfunction "-_-") (pintype "bidirectional"))
    )
    (net (code "39") (name "Net-(BATT171-Pad+)") (class "Default")
      (node (ref "BATT171") (pin "+") (pinfunction "+_+") (pintype "bidirectional"))
      (node (ref "BATT172") (pin "-") (pinfunction "-_-") (pintype "bidirectional"))
    )
    (net (code "40") (name "Net-(BATT172-Pad+)") (class "Default")
      (node (ref "BATT172") (pin "+") (pinfunction "+_+") (pintype "bidirectional"))
      (node (ref "BATT173") (pin "-") (pinfunction "-_-") (pintype "bidirectional"))
    )
    (net (code "41") (name "Net-(BATT173-Pad+)") (class "Default")
      (node (ref "BATT173") (pin "+") (pinfunction "+_+") (pintype "bidirectional"))
      (node (ref "BATT174") (pin "-") (pinfunction "-_-") (pintype "bidirectional"))
    )
    (net (code "42") (name "Net-(BATT174-Pad+)") (class "Default")
      (node (ref "BATT174") (pin "+") (pinfunction "+_+") (pintype "bidirectional"))
      (node (ref "BATT175") (pin "-") (pinfunction "-_-") (pintype "bidirectional"))
    )
    (net (code "43") (name "Net-(BATT175-Pad+)") (class "Default")
      (node (ref "BATT175") (pin "+") (pinfunction "+_+") (pintype "bidirectional"))
      (node (ref "BATT176") (pin "-") (pinfunction "-_-") (pintype "bidirectional"))
    )
    (net (code "44") (name "Net-(BATT176-Pad+)") (class "Default")
      (node (ref "BATT176") (pin "+") (pinfunction "+_+") (pintype "bidirectional"))
      (node (ref "BATT273") (pin "-") (pinfunction "-_-") (pintype "bidirectional"))
    )
    (net (code "45") (name "Net-(BATT177-Pad+)") (class "Default")
      (node (ref "BATT177") (pin "+") (pinfunction "+_+") (pintype "bidirectional"))
      (node (ref "BATT178") (pin "-") (pinfunction "-_-") (pintype "bidirectional"))
    )
    (net (code "46") (name "Net-(BATT177-Pad-)") (class "Default")
      (node (ref "BATT177") (pin "-") (pinfunction "-_-") (pintype "bidirectional"))
      (node (ref "F2") (pin "1") (pinfunction "1_1") (pintype "passive"))
    )
    (net (code "47") (name "Net-(BATT178-Pad+)") (class "Default")
      (node (ref "BATT178") (pin "+") (pinfunction "+_+") (pintype "bidirectional"))
      (node (ref "BATT179") (pin "-") (pinfunction "-_-") (pintype "bidirectional"))
    )
    (net (code "48") (name "Net-(BATT179-Pad+)") (class "Default")
      (node (ref "BATT179") (pin "+") (pinfunction "+_+") (pintype "bidirectional"))
      (node (ref "BATT180") (pin "-") (pinfunction "-_-") (pintype "bidirectional"))
    )
    (net (code "49") (name "Net-(BATT180-Pad+)") (class "Default")
      (node (ref "BATT180") (pin "+") (pinfunction "+_+") (pintype "bidirectional"))
      (node (ref "BATT181") (pin "-") (pinfunction "-_-") (pintype "bidirectional"))
    )
    (net (code "50") (name "Net-(BATT181-Pad+)") (class "Default")
      (node (ref "BATT181") (pin "+") (pinfunction "+_+") (pintype "bidirectional"))
      (node (ref "BATT182") (pin "-") (pinfunction "-_-") (pintype "bidirectional"))
    )
    (net (code "51") (name "Net-(BATT182-Pad+)") (class "Default")
      (node (ref "BATT182") (pin "+") (pinfunction "+_+") (pintype "bidirectional"))
      (node (ref "BATT183") (pin "-") (pinfunction "-_-") (pintype "bidirectional"))
    )
    (net (code "52") (name "Net-(BATT183-Pad+)") (class "Default")
      (node (ref "BATT183") (pin "+") (pinfunction "+_+") (pintype "bidirectional"))
      (node (ref "BATT184") (pin "-") (pinfunction "-_-") (pintype "bidirectional"))
    )
    (net (code "53") (name "Net-(BATT184-Pad+)") (class "Default")
      (node (ref "BATT184") (pin "+") (pinfunction "+_+") (pintype "bidirectional"))
      (node (ref "BATT185") (pin "-") (pinfunction "-_-") (pintype "bidirectional"))
    )
    (net (code "54") (name "Net-(BATT185-Pad+)") (class "Default")
      (node (ref "BATT185") (pin "+") (pinfunction "+_+") (pintype "bidirectional"))
      (node (ref "BATT186") (pin "-") (pinfunction "-_-") (pintype "bidirectional"))
    )
    (net (code "55") (name "Net-(BATT186-Pad+)") (class "Default")
      (node (ref "BATT186") (pin "+") (pinfunction "+_+") (pintype "bidirectional"))
      (node (ref "BATT187") (pin "-") (pinfunction "-_-") (pintype "bidirectional"))
    )
    (net (code "56") (name "Net-(BATT187-Pad+)") (class "Default")
      (node (ref "BATT187") (pin "+") (pinfunction "+_+") (pintype "bidirectional"))
      (node (ref "BATT188") (pin "-") (pinfunction "-_-") (pintype "bidirectional"))
    )
    (net (code "57") (name "Net-(BATT189-Pad+)") (class "Default")
      (node (ref "BATT189") (pin "+") (pinfunction "+_+") (pintype "bidirectional"))
      (node (ref "BATT190") (pin "-") (pinfunction "-_-") (pintype "bidirectional"))
    )
    (net (code "58") (name "Net-(BATT189-Pad-)") (class "Default")
      (node (ref "BATT189") (pin "-") (pinfunction "-_-") (pintype "bidirectional"))
      (node (ref "F4") (pin "1") (pinfunction "1_1") (pintype "passive"))
    )
    (net (code "59") (name "Net-(BATT190-Pad+)") (class "Default")
      (node (ref "BATT190") (pin "+") (pinfunction "+_+") (pintype "bidirectional"))
      (node (ref "BATT191") (pin "-") (pinfunction "-_-") (pintype "bidirectional"))
    )
    (net (code "60") (name "Net-(BATT191-Pad+)") (class "Default")
      (node (ref "BATT191") (pin "+") (pinfunction "+_+") (pintype "bidirectional"))
      (node (ref "BATT192") (pin "-") (pinfunction "-_-") (pintype "bidirectional"))
    )
    (net (code "61") (name "Net-(BATT192-Pad+)") (class "Default")
      (node (ref "BATT192") (pin "+") (pinfunction "+_+") (pintype "bidirectional"))
      (node (ref "BATT193") (pin "-") (pinfunction "-_-") (pintype "bidirectional"))
    )
    (net (code "62") (name "Net-(BATT193-Pad+)") (class "Default")
      (node (ref "BATT193") (pin "+") (pinfunction "+_+") (pintype "bidirectional"))
      (node (ref "BATT194") (pin "-") (pinfunction "-_-") (pintype "bidirectional"))
    )
    (net (code "63") (name "Net-(BATT194-Pad+)") (class "Default")
      (node (ref "BATT194") (pin "+") (pinfunction "+_+") (pintype "bidirectional"))
      (node (ref "BATT195") (pin "-") (pinfunction "-_-") (pintype "bidirectional"))
    )
    (net (code "64") (name "Net-(BATT195-Pad+)") (class "Default")
      (node (ref "BATT195") (pin "+") (pinfunction "+_+") (pintype "bidirectional"))
      (node (ref "BATT196") (pin "-") (pinfunction "-_-") (pintype "bidirectional"))
    )
    (net (code "65") (name "Net-(BATT196-Pad+)") (class "Default")
      (node (ref "BATT196") (pin "+") (pinfunction "+_+") (pintype "bidirectional"))
      (node (ref "BATT197") (pin "-") (pinfunction "-_-") (pintype "bidirectional"))
    )
    (net (code "66") (name "Net-(BATT197-Pad+)") (class "Default")
      (node (ref "BATT197") (pin "+") (pinfunction "+_+") (pintype "bidirectional"))
      (node (ref "BATT198") (pin "-") (pinfunction "-_-") (pintype "bidirectional"))
    )
    (net (code "67") (name "Net-(BATT198-Pad+)") (class "Default")
      (node (ref "BATT198") (pin "+") (pinfunction "+_+") (pintype "bidirectional"))
      (node (ref "BATT199") (pin "-") (pinfunction "-_-") (pintype "bidirectional"))
    )
    (net (code "68") (name "Net-(BATT199-Pad+)") (class "Default")
      (node (ref "BATT199") (pin "+") (pinfunction "+_+") (pintype "bidirectional"))
      (node (ref "BATT200") (pin "-") (pinfunction "-_-") (pintype "bidirectional"))
    )
    (net (code "69") (name "Net-(BATT201-Pad+)") (class "Default")
      (node (ref "BATT201") (pin "+") (pinfunction "+_+") (pintype "bidirectional"))
      (node (ref "BATT202") (pin "-") (pinfunction "-_-") (pintype "bidirectional"))
    )
    (net (code "70") (name "Net-(BATT201-Pad-)") (class "Default")
      (node (ref "BATT201") (pin "-") (pinfunction "-_-") (pintype "bidirectional"))
      (node (ref "F5") (pin "1") (pinfunction "1_1") (pintype "passive"))
    )
    (net (code "71") (name "Net-(BATT202-Pad+)") (class "Default")
      (node (ref "BATT202") (pin "+") (pinfunction "+_+") (pintype "bidirectional"))
      (node (ref "BATT203") (pin "-") (pinfunction "-_-") (pintype "bidirectional"))
    )
    (net (code "72") (name "Net-(BATT203-Pad+)") (class "Default")
      (node (ref "BATT203") (pin "+") (pinfunction "+_+") (pintype "bidirectional"))
      (node (ref "BATT204") (pin "-") (pinfunction "-_-") (pintype "bidirectional"))
    )
    (net (code "73") (name "Net-(BATT204-Pad+)") (class "Default")
      (node (ref "BATT204") (pin "+") (pinfunction "+_+") (pintype "bidirectional"))
      (node (ref "BATT205") (pin "-") (pinfunction "-_-") (pintype "bidirectional"))
    )
    (net (code "74") (name "Net-(BATT205-Pad+)") (class "Default")
      (node (ref "BATT205") (pin "+") (pinfunction "+_+") (pintype "bidirectional"))
      (node (ref "BATT206") (pin "-") (pinfunction "-_-") (pintype "bidirectional"))
    )
    (net (code "75") (name "Net-(BATT206-Pad+)") (class "Default")
      (node (ref "BATT206") (pin "+") (pinfunction "+_+") (pintype "bidirectional"))
      (node (ref "BATT207") (pin "-") (pinfunction "-_-") (pintype "bidirectional"))
    )
    (net (code "76") (name "Net-(BATT207-Pad+)") (class "Default")
      (node (ref "BATT207") (pin "+") (pinfunction "+_+") (pintype "bidirectional"))
      (node (ref "BATT208") (pin "-") (pinfunction "-_-") (pintype "bidirectional"))
    )
    (net (code "77") (name "Net-(BATT208-Pad+)") (class "Default")
      (node (ref "BATT208") (pin "+") (pinfunction "+_+") (pintype "bidirectional"))
      (node (ref "BATT209") (pin "-") (pinfunction "-_-") (pintype "bidirectional"))
    )
    (net (code "78") (name "Net-(BATT209-Pad+)") (class "Default")
      (node (ref "BATT209") (pin "+") (pinfunction "+_+") (pintype "bidirectional"))
      (node (ref "BATT210") (pin "-") (pinfunction "-_-") (pintype "bidirectional"))
    )
    (net (code "79") (name "Net-(BATT210-Pad+)") (class "Default")
      (node (ref "BATT210") (pin "+") (pinfunction "+_+") (pintype "bidirectional"))
      (node (ref "BATT211") (pin "-") (pinfunction "-_-") (pintype "bidirectional"))
    )
    (net (code "80") (name "Net-(BATT211-Pad+)") (class "Default")
      (node (ref "BATT211") (pin "+") (pinfunction "+_+") (pintype "bidirectional"))
      (node (ref "BATT212") (pin "-") (pinfunction "-_-") (pintype "bidirectional"))
    )
    (net (code "81") (name "Net-(BATT213-Pad+)") (class "Default")
      (node (ref "BATT213") (pin "+") (pinfunction "+_+") (pintype "bidirectional"))
      (node (ref "BATT214") (pin "-") (pinfunction "-_-") (pintype "bidirectional"))
    )
    (net (code "82") (name "Net-(BATT213-Pad-)") (class "Default")
      (node (ref "BATT213") (pin "-") (pinfunction "-_-") (pintype "bidirectional"))
      (node (ref "BATT260") (pin "+") (pinfunction "+_+") (pintype "bidirectional"))
    )
    (net (code "83") (name "Net-(BATT214-Pad+)") (class "Default")
      (node (ref "BATT214") (pin "+") (pinfunction "+_+") (pintype "bidirectional"))
      (node (ref "BATT215") (pin "-") (pinfunction "-_-") (pintype "bidirectional"))
    )
    (net (code "84") (name "Net-(BATT215-Pad+)") (class "Default")
      (node (ref "BATT215") (pin "+") (pinfunction "+_+") (pintype "bidirectional"))
      (node (ref "BATT216") (pin "-") (pinfunction "-_-") (pintype "bidirectional"))
    )
    (net (code "85") (name "Net-(BATT216-Pad+)") (class "Default")
      (node (ref "BATT216") (pin "+") (pinfunction "+_+") (pintype "bidirectional"))
      (node (ref "BATT217") (pin "-") (pinfunction "-_-") (pintype "bidirectional"))
    )
    (net (code "86") (name "Net-(BATT217-Pad+)") (class "Default")
      (node (ref "BATT217") (pin "+") (pinfunction "+_+") (pintype "bidirectional"))
      (node (ref "BATT218") (pin "-") (pinfunction "-_-") (pintype "bidirectional"))
    )
    (net (code "87") (name "Net-(BATT218-Pad+)") (class "Default")
      (node (ref "BATT218") (pin "+") (pinfunction "+_+") (pintype "bidirectional"))
      (node (ref "BATT219") (pin "-") (pinfunction "-_-") (pintype "bidirectional"))
    )
    (net (code "88") (name "Net-(BATT219-Pad+)") (class "Default")
      (node (ref "BATT219") (pin "+") (pinfunction "+_+") (pintype "bidirectional"))
      (node (ref "BATT220") (pin "-") (pinfunction "-_-") (pintype "bidirectional"))
    )
    (net (code "89") (name "Net-(BATT220-Pad+)") (class "Default")
      (node (ref "BATT220") (pin "+") (pinfunction "+_+") (pintype "bidirectional"))
      (node (ref "BATT221") (pin "-") (pinfunction "-_-") (pintype "bidirectional"))
    )
    (net (code "90") (name "Net-(BATT221-Pad+)") (class "Default")
      (node (ref "BATT221") (pin "+") (pinfunction "+_+") (pintype "bidirectional"))
      (node (ref "BATT222") (pin "-") (pinfunction "-_-") (pintype "bidirectional"))
    )
    (net (code "91") (name "Net-(BATT222-Pad+)") (class "Default")
      (node (ref "BATT222") (pin "+") (pinfunction "+_+") (pintype "bidirectional"))
      (node (ref "BATT223") (pin "-") (pinfunction "-_-") (pintype "bidirectional"))
    )
    (net (code "92") (name "Net-(BATT223-Pad+)") (class "Default")
      (node (ref "BATT223") (pin "+") (pinfunction "+_+") (pintype "bidirectional"))
      (node (ref "BATT224") (pin "-") (pinfunction "-_-") (pintype "bidirectional"))
    )
    (net (code "93") (name "Net-(BATT224-Pad+)") (class "Default")
      (node (ref "BATT224") (pin "+") (pinfunction "+_+") (pintype "bidirectional"))
      (node (ref "BATT321") (pin "-") (pinfunction "-_-") (pintype "bidirectional"))
    )
    (net (code "94") (name "Net-(BATT225-Pad+)") (class "Default")
      (node (ref "BATT225") (pin "+") (pinfunction "+_+") (pintype "bidirectional"))
      (node (ref "BATT226") (pin "-") (pinfunction "-_-") (pintype "bidirectional"))
    )
    (net (code "95") (name "Net-(BATT225-Pad-)") (class "Default")
      (node (ref "BATT225") (pin "-") (pinfunction "-_-") (pintype "bidirectional"))
      (node (ref "BATT272") (pin "+") (pinfunction "+_+") (pintype "bidirectional"))
    )
    (net (code "96") (name "Net-(BATT226-Pad+)") (class "Default")
      (node (ref "BATT226") (pin "+") (pinfunction "+_+") (pintype "bidirectional"))
      (node (ref "BATT227") (pin "-") (pinfunction "-_-") (pintype "bidirectional"))
    )
    (net (code "97") (name "Net-(BATT227-Pad+)") (class "Default")
      (node (ref "BATT227") (pin "+") (pinfunction "+_+") (pintype "bidirectional"))
      (node (ref "BATT228") (pin "-") (pinfunction "-_-") (pintype "bidirectional"))
    )
    (net (code "98") (name "Net-(BATT228-Pad+)") (class "Default")
      (node (ref "BATT228") (pin "+") (pinfunction "+_+") (pintype "bidirectional"))
      (node (ref "BATT229") (pin "-") (pinfunction "-_-") (pintype "bidirectional"))
    )
    (net (code "99") (name "Net-(BATT229-Pad+)") (class "Default")
      (node (ref "BATT229") (pin "+") (pinfunction "+_+") (pintype "bidirectional"))
      (node (ref "BATT230") (pin "-") (pinfunction "-_-") (pintype "bidirectional"))
    )
    (net (code "100") (name "Net-(BATT230-Pad+)") (class "Default")
      (node (ref "BATT230") (pin "+") (pinfunction "+_+") (pintype "bidirectional"))
      (node (ref "BATT231") (pin "-") (pinfunction "-_-") (pintype "bidirectional"))
    )
    (net (code "101") (name "Net-(BATT231-Pad+)") (class "Default")
      (node (ref "BATT231") (pin "+") (pinfunction "+_+") (pintype "bidirectional"))
      (node (ref "BATT232") (pin "-") (pinfunction "-_-") (pintype "bidirectional"))
    )
    (net (code "102") (name "Net-(BATT232-Pad+)") (class "Default")
      (node (ref "BATT232") (pin "+") (pinfunction "+_+") (pintype "bidirectional"))
      (node (ref "BATT233") (pin "-") (pinfunction "-_-") (pintype "bidirectional"))
    )
    (net (code "103") (name "Net-(BATT233-Pad+)") (class "Default")
      (node (ref "BATT233") (pin "+") (pinfunction "+_+") (pintype "bidirectional"))
      (node (ref "BATT234") (pin "-") (pinfunction "-_-") (pintype "bidirectional"))
    )
    (net (code "104") (name "Net-(BATT234-Pad+)") (class "Default")
      (node (ref "BATT234") (pin "+") (pinfunction "+_+") (pintype "bidirectional"))
      (node (ref "BATT235") (pin "-") (pinfunction "-_-") (pintype "bidirectional"))
    )
    (net (code "105") (name "Net-(BATT235-Pad+)") (class "Default")
      (node (ref "BATT235") (pin "+") (pinfunction "+_+") (pintype "bidirectional"))
      (node (ref "BATT236") (pin "-") (pinfunction "-_-") (pintype "bidirectional"))
    )
    (net (code "106") (name "Net-(BATT236-Pad+)") (class "Default")
      (node (ref "BATT236") (pin "+") (pinfunction "+_+") (pintype "bidirectional"))
      (node (ref "BATT333") (pin "-") (pinfunction "-_-") (pintype "bidirectional"))
    )
    (net (code "107") (name "Net-(BATT237-Pad+)") (class "Default")
      (node (ref "BATT237") (pin "+") (pinfunction "+_+") (pintype "bidirectional"))
      (node (ref "BATT238") (pin "-") (pinfunction "-_-") (pintype "bidirectional"))
    )
    (net (code "108") (name "Net-(BATT237-Pad-)") (class "Default")
      (node (ref "BATT237") (pin "-") (pinfunction "-_-") (pintype "bidirectional"))
      (node (ref "BATT284") (pin "+") (pinfunction "+_+") (pintype "bidirectional"))
    )
    (net (code "109") (name "Net-(BATT238-Pad+)") (class "Default")
      (node (ref "BATT238") (pin "+") (pinfunction "+_+") (pintype "bidirectional"))
      (node (ref "BATT239") (pin "-") (pinfunction "-_-") (pintype "bidirectional"))
    )
    (net (code "110") (name "Net-(BATT239-Pad+)") (class "Default")
      (node (ref "BATT239") (pin "+") (pinfunction "+_+") (pintype "bidirectional"))
      (node (ref "BATT240") (pin "-") (pinfunction "-_-") (pintype "bidirectional"))
    )
    (net (code "111") (name "Net-(BATT240-Pad+)") (class "Default")
      (node (ref "BATT240") (pin "+") (pinfunction "+_+") (pintype "bidirectional"))
      (node (ref "BATT241") (pin "-") (pinfunction "-_-") (pintype "bidirectional"))
    )
    (net (code "112") (name "Net-(BATT241-Pad+)") (class "Default")
      (node (ref "BATT241") (pin "+") (pinfunction "+_+") (pintype "bidirectional"))
      (node (ref "BATT242") (pin "-") (pinfunction "-_-") (pintype "bidirectional"))
    )
    (net (code "113") (name "Net-(BATT242-Pad+)") (class "Default")
      (node (ref "BATT242") (pin "+") (pinfunction "+_+") (pintype "bidirectional"))
      (node (ref "BATT243") (pin "-") (pinfunction "-_-") (pintype "bidirectional"))
    )
    (net (code "114") (name "Net-(BATT243-Pad+)") (class "Default")
      (node (ref "BATT243") (pin "+") (pinfunction "+_+") (pintype "bidirectional"))
      (node (ref "BATT244") (pin "-") (pinfunction "-_-") (pintype "bidirectional"))
    )
    (net (code "115") (name "Net-(BATT244-Pad+)") (class "Default")
      (node (ref "BATT244") (pin "+") (pinfunction "+_+") (pintype "bidirectional"))
      (node (ref "BATT245") (pin "-") (pinfunction "-_-") (pintype "bidirectional"))
    )
    (net (code "116") (name "Net-(BATT245-Pad+)") (class "Default")
      (node (ref "BATT245") (pin "+") (pinfunction "+_+") (pintype "bidirectional"))
      (node (ref "BATT246") (pin "-") (pinfunction "-_-") (pintype "bidirectional"))
    )
    (net (code "117") (name "Net-(BATT246-Pad+)") (class "Default")
      (node (ref "BATT246") (pin "+") (pinfunction "+_+") (pintype "bidirectional"))
      (node (ref "BATT247") (pin "-") (pinfunction "-_-") (pintype "bidirectional"))
    )
    (net (code "118") (name "Net-(BATT247-Pad+)") (class "Default")
      (node (ref "BATT247") (pin "+") (pinfunction "+_+") (pintype "bidirectional"))
      (node (ref "BATT248") (pin "-") (pinfunction "-_-") (pintype "bidirectional"))
    )
    (net (code "119") (name "Net-(BATT248-Pad+)") (class "Default")
      (node (ref "BATT248") (pin "+") (pinfunction "+_+") (pintype "bidirectional"))
      (node (ref "BATT345") (pin "-") (pinfunction "-_-") (pintype "bidirectional"))
    )
    (net (code "120") (name "Net-(BATT249-Pad+)") (class "Default")
      (node (ref "BATT249") (pin "+") (pinfunction "+_+") (pintype "bidirectional"))
      (node (ref "BATT250") (pin "-") (pinfunction "-_-") (pintype "bidirectional"))
    )
    (net (code "121") (name "Net-(BATT250-Pad+)") (class "Default")
      (node (ref "BATT250") (pin "+") (pinfunction "+_+") (pintype "bidirectional"))
      (node (ref "BATT251") (pin "-") (pinfunction "-_-") (pintype "bidirectional"))
    )
    (net (code "122") (name "Net-(BATT251-Pad+)") (class "Default")
      (node (ref "BATT251") (pin "+") (pinfunction "+_+") (pintype "bidirectional"))
      (node (ref "BATT252") (pin "-") (pinfunction "-_-") (pintype "bidirectional"))
    )
    (net (code "123") (name "Net-(BATT252-Pad+)") (class "Default")
      (node (ref "BATT252") (pin "+") (pinfunction "+_+") (pintype "bidirectional"))
      (node (ref "BATT253") (pin "-") (pinfunction "-_-") (pintype "bidirectional"))
    )
    (net (code "124") (name "Net-(BATT253-Pad+)") (class "Default")
      (node (ref "BATT253") (pin "+") (pinfunction "+_+") (pintype "bidirectional"))
      (node (ref "BATT254") (pin "-") (pinfunction "-_-") (pintype "bidirectional"))
    )
    (net (code "125") (name "Net-(BATT254-Pad+)") (class "Default")
      (node (ref "BATT254") (pin "+") (pinfunction "+_+") (pintype "bidirectional"))
      (node (ref "BATT255") (pin "-") (pinfunction "-_-") (pintype "bidirectional"))
    )
    (net (code "126") (name "Net-(BATT255-Pad+)") (class "Default")
      (node (ref "BATT255") (pin "+") (pinfunction "+_+") (pintype "bidirectional"))
      (node (ref "BATT256") (pin "-") (pinfunction "-_-") (pintype "bidirectional"))
    )
    (net (code "127") (name "Net-(BATT256-Pad+)") (class "Default")
      (node (ref "BATT256") (pin "+") (pinfunction "+_+") (pintype "bidirectional"))
      (node (ref "BATT257") (pin "-") (pinfunction "-_-") (pintype "bidirectional"))
    )
    (net (code "128") (name "Net-(BATT257-Pad+)") (class "Default")
      (node (ref "BATT257") (pin "+") (pinfunction "+_+") (pintype "bidirectional"))
      (node (ref "BATT258") (pin "-") (pinfunction "-_-") (pintype "bidirectional"))
    )
    (net (code "129") (name "Net-(BATT258-Pad+)") (class "Default")
      (node (ref "BATT258") (pin "+") (pinfunction "+_+") (pintype "bidirectional"))
      (node (ref "BATT259") (pin "-") (pinfunction "-_-") (pintype "bidirectional"))
    )
    (net (code "130") (name "Net-(BATT259-Pad+)") (class "Default")
      (node (ref "BATT259") (pin "+") (pinfunction "+_+") (pintype "bidirectional"))
      (node (ref "BATT260") (pin "-") (pinfunction "-_-") (pintype "bidirectional"))
    )
    (net (code "131") (name "Net-(BATT261-Pad+)") (class "Default")
      (node (ref "BATT261") (pin "+") (pinfunction "+_+") (pintype "bidirectional"))
      (node (ref "BATT262") (pin "-") (pinfunction "-_-") (pintype "bidirectional"))
    )
    (net (code "132") (name "Net-(BATT262-Pad+)") (class "Default")
      (node (ref "BATT262") (pin "+") (pinfunction "+_+") (pintype "bidirectional"))
      (node (ref "BATT263") (pin "-") (pinfunction "-_-") (pintype "bidirectional"))
    )
    (net (code "133") (name "Net-(BATT263-Pad+)") (class "Default")
      (node (ref "BATT263") (pin "+") (pinfunction "+_+") (pintype "bidirectional"))
      (node (ref "BATT264") (pin "-") (pinfunction "-_-") (pintype "bidirectional"))
    )
    (net (code "134") (name "Net-(BATT264-Pad+)") (class "Default")
      (node (ref "BATT264") (pin "+") (pinfunction "+_+") (pintype "bidirectional"))
      (node (ref "BATT265") (pin "-") (pinfunction "-_-") (pintype "bidirectional"))
    )
    (net (code "135") (name "Net-(BATT265-Pad+)") (class "Default")
      (node (ref "BATT265") (pin "+") (pinfunction "+_+") (pintype "bidirectional"))
      (node (ref "BATT266") (pin "-") (pinfunction "-_-") (pintype "bidirectional"))
    )
    (net (code "136") (name "Net-(BATT266-Pad+)") (class "Default")
      (node (ref "BATT266") (pin "+") (pinfunction "+_+") (pintype "bidirectional"))
      (node (ref "BATT267") (pin "-") (pinfunction "-_-") (pintype "bidirectional"))
    )
    (net (code "137") (name "Net-(BATT267-Pad+)") (class "Default")
      (node (ref "BATT267") (pin "+") (pinfunction "+_+") (pintype "bidirectional"))
      (node (ref "BATT268") (pin "-") (pinfunction "-_-") (pintype "bidirectional"))
    )
    (net (code "138") (name "Net-(BATT268-Pad+)") (class "Default")
      (node (ref "BATT268") (pin "+") (pinfunction "+_+") (pintype "bidirectional"))
      (node (ref "BATT269") (pin "-") (pinfunction "-_-") (pintype "bidirectional"))
    )
    (net (code "139") (name "Net-(BATT269-Pad+)") (class "Default")
      (node (ref "BATT269") (pin "+") (pinfunction "+_+") (pintype "bidirectional"))
      (node (ref "BATT270") (pin "-") (pinfunction "-_-") (pintype "bidirectional"))
    )
    (net (code "140") (name "Net-(BATT270-Pad+)") (class "Default")
      (node (ref "BATT270") (pin "+") (pinfunction "+_+") (pintype "bidirectional"))
      (node (ref "BATT271") (pin "-") (pinfunction "-_-") (pintype "bidirectional"))
    )
    (net (code "141") (name "Net-(BATT271-Pad+)") (class "Default")
      (node (ref "BATT271") (pin "+") (pinfunction "+_+") (pintype "bidirectional"))
      (node (ref "BATT272") (pin "-") (pinfunction "-_-") (pintype "bidirectional"))
    )
    (net (code "142") (name "Net-(BATT273-Pad+)") (class "Default")
      (node (ref "BATT273") (pin "+") (pinfunction "+_+") (pintype "bidirectional"))
      (node (ref "BATT274") (pin "-") (pinfunction "-_-") (pintype "bidirectional"))
    )
    (net (code "143") (name "Net-(BATT274-Pad+)") (class "Default")
      (node (ref "BATT274") (pin "+") (pinfunction "+_+") (pintype "bidirectional"))
      (node (ref "BATT275") (pin "-") (pinfunction "-_-") (pintype "bidirectional"))
    )
    (net (code "144") (name "Net-(BATT275-Pad+)") (class "Default")
      (node (ref "BATT275") (pin "+") (pinfunction "+_+") (pintype "bidirectional"))
      (node (ref "BATT276") (pin "-") (pinfunction "-_-") (pintype "bidirectional"))
    )
    (net (code "145") (name "Net-(BATT276-Pad+)") (class "Default")
      (node (ref "BATT276") (pin "+") (pinfunction "+_+") (pintype "bidirectional"))
      (node (ref "BATT277") (pin "-") (pinfunction "-_-") (pintype "bidirectional"))
    )
    (net (code "146") (name "Net-(BATT277-Pad+)") (class "Default")
      (node (ref "BATT277") (pin "+") (pinfunction "+_+") (pintype "bidirectional"))
      (node (ref "BATT278") (pin "-") (pinfunction "-_-") (pintype "bidirectional"))
    )
    (net (code "147") (name "Net-(BATT278-Pad+)") (class "Default")
      (node (ref "BATT278") (pin "+") (pinfunction "+_+") (pintype "bidirectional"))
      (node (ref "BATT279") (pin "-") (pinfunction "-_-") (pintype "bidirectional"))
    )
    (net (code "148") (name "Net-(BATT279-Pad+)") (class "Default")
      (node (ref "BATT279") (pin "+") (pinfunction "+_+") (pintype "bidirectional"))
      (node (ref "BATT280") (pin "-") (pinfunction "-_-") (pintype "bidirectional"))
    )
    (net (code "149") (name "Net-(BATT280-Pad+)") (class "Default")
      (node (ref "BATT280") (pin "+") (pinfunction "+_+") (pintype "bidirectional"))
      (node (ref "BATT281") (pin "-") (pinfunction "-_-") (pintype "bidirectional"))
    )
    (net (code "150") (name "Net-(BATT281-Pad+)") (class "Default")
      (node (ref "BATT281") (pin "+") (pinfunction "+_+") (pintype "bidirectional"))
      (node (ref "BATT282") (pin "-") (pinfunction "-_-") (pintype "bidirectional"))
    )
    (net (code "151") (name "Net-(BATT282-Pad+)") (class "Default")
      (node (ref "BATT282") (pin "+") (pinfunction "+_+") (pintype "bidirectional"))
      (node (ref "BATT283") (pin "-") (pinfunction "-_-") (pintype "bidirectional"))
    )
    (net (code "152") (name "Net-(BATT283-Pad+)") (class "Default")
      (node (ref "BATT283") (pin "+") (pinfunction "+_+") (pintype "bidirectional"))
      (node (ref "BATT284") (pin "-") (pinfunction "-_-") (pintype "bidirectional"))
    )
    (net (code "153") (name "Net-(BATT285-Pad+)") (class "Default")
      (node (ref "BATT285") (pin "+") (pinfunction "+_+") (pintype "bidirectional"))
      (node (ref "BATT286") (pin "-") (pinfunction "-_-") (pintype "bidirectional"))
    )
    (net (code "154") (name "Net-(BATT285-Pad-)") (class "Default")
      (node (ref "BATT285") (pin "-") (pinfunction "-_-") (pintype "bidirectional"))
      (node (ref "BATT332") (pin "+") (pinfunction "+_+") (pintype "bidirectional"))
    )
    (net (code "155") (name "Net-(BATT286-Pad+)") (class "Default")
      (node (ref "BATT286") (pin "+") (pinfunction "+_+") (pintype "bidirectional"))
      (node (ref "BATT287") (pin "-") (pinfunction "-_-") (pintype "bidirectional"))
    )
    (net (code "156") (name "Net-(BATT287-Pad+)") (class "Default")
      (node (ref "BATT287") (pin "+") (pinfunction "+_+") (pintype "bidirectional"))
      (node (ref "BATT288") (pin "-") (pinfunction "-_-") (pintype "bidirectional"))
    )
    (net (code "157") (name "Net-(BATT288-Pad+)") (class "Default")
      (node (ref "BATT288") (pin "+") (pinfunction "+_+") (pintype "bidirectional"))
      (node (ref "BATT289") (pin "-") (pinfunction "-_-") (pintype "bidirectional"))
    )
    (net (code "158") (name "Net-(BATT289-Pad+)") (class "Default")
      (node (ref "BATT289") (pin "+") (pinfunction "+_+") (pintype "bidirectional"))
      (node (ref "BATT290") (pin "-") (pinfunction "-_-") (pintype "bidirectional"))
    )
    (net (code "159") (name "Net-(BATT290-Pad+)") (class "Default")
      (node (ref "BATT290") (pin "+") (pinfunction "+_+") (pintype "bidirectional"))
      (node (ref "BATT291") (pin "-") (pinfunction "-_-") (pintype "bidirectional"))
    )
    (net (code "160") (name "Net-(BATT291-Pad+)") (class "Default")
      (node (ref "BATT291") (pin "+") (pinfunction "+_+") (pintype "bidirectional"))
      (node (ref "BATT292") (pin "-") (pinfunction "-_-") (pintype "bidirectional"))
    )
    (net (code "161") (name "Net-(BATT292-Pad+)") (class "Default")
      (node (ref "BATT292") (pin "+") (pinfunction "+_+") (pintype "bidirectional"))
      (node (ref "BATT293") (pin "-") (pinfunction "-_-") (pintype "bidirectional"))
    )
    (net (code "162") (name "Net-(BATT293-Pad+)") (class "Default")
      (node (ref "BATT293") (pin "+") (pinfunction "+_+") (pintype "bidirectional"))
      (node (ref "BATT294") (pin "-") (pinfunction "-_-") (pintype "bidirectional"))
    )
    (net (code "163") (name "Net-(BATT294-Pad+)") (class "Default")
      (node (ref "BATT294") (pin "+") (pinfunction "+_+") (pintype "bidirectional"))
      (node (ref "BATT295") (pin "-") (pinfunction "-_-") (pintype "bidirectional"))
    )
    (net (code "164") (name "Net-(BATT295-Pad+)") (class "Default")
      (node (ref "BATT295") (pin "+") (pinfunction "+_+") (pintype "bidirectional"))
      (node (ref "BATT296") (pin "-") (pinfunction "-_-") (pintype "bidirectional"))
    )
    (net (code "165") (name "Net-(BATT297-Pad+)") (class "Default")
      (node (ref "BATT297") (pin "+") (pinfunction "+_+") (pintype "bidirectional"))
      (node (ref "BATT298") (pin "-") (pinfunction "-_-") (pintype "bidirectional"))
    )
    (net (code "166") (name "Net-(BATT297-Pad-)") (class "Default")
      (node (ref "BATT297") (pin "-") (pinfunction "-_-") (pintype "bidirectional"))
      (node (ref "BATT344") (pin "+") (pinfunction "+_+") (pintype "bidirectional"))
    )
    (net (code "167") (name "Net-(BATT298-Pad+)") (class "Default")
      (node (ref "BATT298") (pin "+") (pinfunction "+_+") (pintype "bidirectional"))
      (node (ref "BATT299") (pin "-") (pinfunction "-_-") (pintype "bidirectional"))
    )
    (net (code "168") (name "Net-(BATT299-Pad+)") (class "Default")
      (node (ref "BATT299") (pin "+") (pinfunction "+_+") (pintype "bidirectional"))
      (node (ref "BATT300") (pin "-") (pinfunction "-_-") (pintype "bidirectional"))
    )
    (net (code "169") (name "Net-(BATT300-Pad+)") (class "Default")
      (node (ref "BATT300") (pin "+") (pinfunction "+_+") (pintype "bidirectional"))
      (node (ref "BATT301") (pin "-") (pinfunction "-_-") (pintype "bidirectional"))
    )
    (net (code "170") (name "Net-(BATT301-Pad+)") (class "Default")
      (node (ref "BATT301") (pin "+") (pinfunction "+_+") (pintype "bidirectional"))
      (node (ref "BATT302") (pin "-") (pinfunction "-_-") (pintype "bidirectional"))
    )
    (net (code "171") (name "Net-(BATT302-Pad+)") (class "Default")
      (node (ref "BATT302") (pin "+") (pinfunction "+_+") (pintype "bidirectional"))
      (node (ref "BATT303") (pin "-") (pinfunction "-_-") (pintype "bidirectional"))
    )
    (net (code "172") (name "Net-(BATT303-Pad+)") (class "Default")
      (node (ref "BATT303") (pin "+") (pinfunction "+_+") (pintype "bidirectional"))
      (node (ref "BATT304") (pin "-") (pinfunction "-_-") (pintype "bidirectional"))
    )
    (net (code "173") (name "Net-(BATT304-Pad+)") (class "Default")
      (node (ref "BATT304") (pin "+") (pinfunction "+_+") (pintype "bidirectional"))
      (node (ref "BATT305") (pin "-") (pinfunction "-_-") (pintype "bidirectional"))
    )
    (net (code "174") (name "Net-(BATT305-Pad+)") (class "Default")
      (node (ref "BATT305") (pin "+") (pinfunction "+_+") (pintype "bidirectional"))
      (node (ref "BATT306") (pin "-") (pinfunction "-_-") (pintype "bidirectional"))
    )
    (net (code "175") (name "Net-(BATT306-Pad+)") (class "Default")
      (node (ref "BATT306") (pin "+") (pinfunction "+_+") (pintype "bidirectional"))
      (node (ref "BATT307") (pin "-") (pinfunction "-_-") (pintype "bidirectional"))
    )
    (net (code "176") (name "Net-(BATT307-Pad+)") (class "Default")
      (node (ref "BATT307") (pin "+") (pinfunction "+_+") (pintype "bidirectional"))
      (node (ref "BATT308") (pin "-") (pinfunction "-_-") (pintype "bidirectional"))
    )
    (net (code "177") (name "Net-(BATT309-Pad+)") (class "Default")
      (node (ref "BATT309") (pin "+") (pinfunction "+_+") (pintype "bidirectional"))
      (node (ref "BATT310") (pin "-") (pinfunction "-_-") (pintype "bidirectional"))
    )
    (net (code "178") (name "Net-(BATT309-Pad-)") (class "Default")
      (node (ref "BATT309") (pin "-") (pinfunction "-_-") (pintype "bidirectional"))
      (node (ref "BATT356") (pin "+") (pinfunction "+_+") (pintype "bidirectional"))
    )
    (net (code "179") (name "Net-(BATT310-Pad+)") (class "Default")
      (node (ref "BATT310") (pin "+") (pinfunction "+_+") (pintype "bidirectional"))
      (node (ref "BATT311") (pin "-") (pinfunction "-_-") (pintype "bidirectional"))
    )
    (net (code "180") (name "Net-(BATT311-Pad+)") (class "Default")
      (node (ref "BATT311") (pin "+") (pinfunction "+_+") (pintype "bidirectional"))
      (node (ref "BATT312") (pin "-") (pinfunction "-_-") (pintype "bidirectional"))
    )
    (net (code "181") (name "Net-(BATT312-Pad+)") (class "Default")
      (node (ref "BATT312") (pin "+") (pinfunction "+_+") (pintype "bidirectional"))
      (node (ref "BATT313") (pin "-") (pinfunction "-_-") (pintype "bidirectional"))
    )
    (net (code "182") (name "Net-(BATT313-Pad+)") (class "Default")
      (node (ref "BATT313") (pin "+") (pinfunction "+_+") (pintype "bidirectional"))
      (node (ref "BATT314") (pin "-") (pinfunction "-_-") (pintype "bidirectional"))
    )
    (net (code "183") (name "Net-(BATT314-Pad+)") (class "Default")
      (node (ref "BATT314") (pin "+") (pinfunction "+_+") (pintype "bidirectional"))
      (node (ref "BATT315") (pin "-") (pinfunction "-_-") (pintype "bidirectional"))
    )
    (net (code "184") (name "Net-(BATT315-Pad+)") (class "Default")
      (node (ref "BATT315") (pin "+") (pinfunction "+_+") (pintype "bidirectional"))
      (node (ref "BATT316") (pin "-") (pinfunction "-_-") (pintype "bidirectional"))
    )
    (net (code "185") (name "Net-(BATT316-Pad+)") (class "Default")
      (node (ref "BATT316") (pin "+") (pinfunction "+_+") (pintype "bidirectional"))
      (node (ref "BATT317") (pin "-") (pinfunction "-_-") (pintype "bidirectional"))
    )
    (net (code "186") (name "Net-(BATT317-Pad+)") (class "Default")
      (node (ref "BATT317") (pin "+") (pinfunction "+_+") (pintype "bidirectional"))
      (node (ref "BATT318") (pin "-") (pinfunction "-_-") (pintype "bidirectional"))
    )
    (net (code "187") (name "Net-(BATT318-Pad+)") (class "Default")
      (node (ref "BATT318") (pin "+") (pinfunction "+_+") (pintype "bidirectional"))
      (node (ref "BATT319") (pin "-") (pinfunction "-_-") (pintype "bidirectional"))
    )
    (net (code "188") (name "Net-(BATT319-Pad+)") (class "Default")
      (node (ref "BATT319") (pin "+") (pinfunction "+_+") (pintype "bidirectional"))
      (node (ref "BATT320") (pin "-") (pinfunction "-_-") (pintype "bidirectional"))
    )
    (net (code "189") (name "Net-(BATT321-Pad+)") (class "Default")
      (node (ref "BATT321") (pin "+") (pinfunction "+_+") (pintype "bidirectional"))
      (node (ref "BATT322") (pin "-") (pinfunction "-_-") (pintype "bidirectional"))
    )
    (net (code "190") (name "Net-(BATT322-Pad+)") (class "Default")
      (node (ref "BATT322") (pin "+") (pinfunction "+_+") (pintype "bidirectional"))
      (node (ref "BATT323") (pin "-") (pinfunction "-_-") (pintype "bidirectional"))
    )
    (net (code "191") (name "Net-(BATT323-Pad+)") (class "Default")
      (node (ref "BATT323") (pin "+") (pinfunction "+_+") (pintype "bidirectional"))
      (node (ref "BATT324") (pin "-") (pinfunction "-_-") (pintype "bidirectional"))
    )
    (net (code "192") (name "Net-(BATT324-Pad+)") (class "Default")
      (node (ref "BATT324") (pin "+") (pinfunction "+_+") (pintype "bidirectional"))
      (node (ref "BATT325") (pin "-") (pinfunction "-_-") (pintype "bidirectional"))
    )
    (net (code "193") (name "Net-(BATT325-Pad+)") (class "Default")
      (node (ref "BATT325") (pin "+") (pinfunction "+_+") (pintype "bidirectional"))
      (node (ref "BATT326") (pin "-") (pinfunction "-_-") (pintype "bidirectional"))
    )
    (net (code "194") (name "Net-(BATT326-Pad+)") (class "Default")
      (node (ref "BATT326") (pin "+") (pinfunction "+_+") (pintype "bidirectional"))
      (node (ref "BATT327") (pin "-") (pinfunction "-_-") (pintype "bidirectional"))
    )
    (net (code "195") (name "Net-(BATT327-Pad+)") (class "Default")
      (node (ref "BATT327") (pin "+") (pinfunction "+_+") (pintype "bidirectional"))
      (node (ref "BATT328") (pin "-") (pinfunction "-_-") (pintype "bidirectional"))
    )
    (net (code "196") (name "Net-(BATT328-Pad+)") (class "Default")
      (node (ref "BATT328") (pin "+") (pinfunction "+_+") (pintype "bidirectional"))
      (node (ref "BATT329") (pin "-") (pinfunction "-_-") (pintype "bidirectional"))
    )
    (net (code "197") (name "Net-(BATT329-Pad+)") (class "Default")
      (node (ref "BATT329") (pin "+") (pinfunction "+_+") (pintype "bidirectional"))
      (node (ref "BATT330") (pin "-") (pinfunction "-_-") (pintype "bidirectional"))
    )
    (net (code "198") (name "Net-(BATT330-Pad+)") (class "Default")
      (node (ref "BATT330") (pin "+") (pinfunction "+_+") (pintype "bidirectional"))
      (node (ref "BATT331") (pin "-") (pinfunction "-_-") (pintype "bidirectional"))
    )
    (net (code "199") (name "Net-(BATT331-Pad+)") (class "Default")
      (node (ref "BATT331") (pin "+") (pinfunction "+_+") (pintype "bidirectional"))
      (node (ref "BATT332") (pin "-") (pinfunction "-_-") (pintype "bidirectional"))
    )
    (net (code "200") (name "Net-(BATT333-Pad+)") (class "Default")
      (node (ref "BATT333") (pin "+") (pinfunction "+_+") (pintype "bidirectional"))
      (node (ref "BATT334") (pin "-") (pinfunction "-_-") (pintype "bidirectional"))
    )
    (net (code "201") (name "Net-(BATT334-Pad+)") (class "Default")
      (node (ref "BATT334") (pin "+") (pinfunction "+_+") (pintype "bidirectional"))
      (node (ref "BATT335") (pin "-") (pinfunction "-_-") (pintype "bidirectional"))
    )
    (net (code "202") (name "Net-(BATT335-Pad+)") (class "Default")
      (node (ref "BATT335") (pin "+") (pinfunction "+_+") (pintype "bidirectional"))
      (node (ref "BATT336") (pin "-") (pinfunction "-_-") (pintype "bidirectional"))
    )
    (net (code "203") (name "Net-(BATT336-Pad+)") (class "Default")
      (node (ref "BATT336") (pin "+") (pinfunction "+_+") (pintype "bidirectional"))
      (node (ref "BATT337") (pin "-") (pinfunction "-_-") (pintype "bidirectional"))
    )
    (net (code "204") (name "Net-(BATT337-Pad+)") (class "Default")
      (node (ref "BATT337") (pin "+") (pinfunction "+_+") (pintype "bidirectional"))
      (node (ref "BATT338") (pin "-") (pinfunction "-_-") (pintype "bidirectional"))
    )
    (net (code "205") (name "Net-(BATT338-Pad+)") (class "Default")
      (node (ref "BATT338") (pin "+") (pinfunction "+_+") (pintype "bidirectional"))
      (node (ref "BATT339") (pin "-") (pinfunction "-_-") (pintype "bidirectional"))
    )
    (net (code "206") (name "Net-(BATT339-Pad+)") (class "Default")
      (node (ref "BATT339") (pin "+") (pinfunction "+_+") (pintype "bidirectional"))
      (node (ref "BATT340") (pin "-") (pinfunction "-_-") (pintype "bidirectional"))
    )
    (net (code "207") (name "Net-(BATT340-Pad+)") (class "Default")
      (node (ref "BATT340") (pin "+") (pinfunction "+_+") (pintype "bidirectional"))
      (node (ref "BATT341") (pin "-") (pinfunction "-_-") (pintype "bidirectional"))
    )
    (net (code "208") (name "Net-(BATT341-Pad+)") (class "Default")
      (node (ref "BATT341") (pin "+") (pinfunction "+_+") (pintype "bidirectional"))
      (node (ref "BATT342") (pin "-") (pinfunction "-_-") (pintype "bidirectional"))
    )
    (net (code "209") (name "Net-(BATT342-Pad+)") (class "Default")
      (node (ref "BATT342") (pin "+") (pinfunction "+_+") (pintype "bidirectional"))
      (node (ref "BATT343") (pin "-") (pinfunction "-_-") (pintype "bidirectional"))
    )
    (net (code "210") (name "Net-(BATT343-Pad+)") (class "Default")
      (node (ref "BATT343") (pin "+") (pinfunction "+_+") (pintype "bidirectional"))
      (node (ref "BATT344") (pin "-") (pinfunction "-_-") (pintype "bidirectional"))
    )
    (net (code "211") (name "Net-(BATT345-Pad+)") (class "Default")
      (node (ref "BATT345") (pin "+") (pinfunction "+_+") (pintype "bidirectional"))
      (node (ref "BATT346") (pin "-") (pinfunction "-_-") (pintype "bidirectional"))
    )
    (net (code "212") (name "Net-(BATT346-Pad+)") (class "Default")
      (node (ref "BATT346") (pin "+") (pinfunction "+_+") (pintype "bidirectional"))
      (node (ref "BATT347") (pin "-") (pinfunction "-_-") (pintype "bidirectional"))
    )
    (net (code "213") (name "Net-(BATT347-Pad+)") (class "Default")
      (node (ref "BATT347") (pin "+") (pinfunction "+_+") (pintype "bidirectional"))
      (node (ref "BATT348") (pin "-") (pinfunction "-_-") (pintype "bidirectional"))
    )
    (net (code "214") (name "Net-(BATT348-Pad+)") (class "Default")
      (node (ref "BATT348") (pin "+") (pinfunction "+_+") (pintype "bidirectional"))
      (node (ref "BATT349") (pin "-") (pinfunction "-_-") (pintype "bidirectional"))
    )
    (net (code "215") (name "Net-(BATT349-Pad+)") (class "Default")
      (node (ref "BATT349") (pin "+") (pinfunction "+_+") (pintype "bidirectional"))
      (node (ref "BATT350") (pin "-") (pinfunction "-_-") (pintype "bidirectional"))
    )
    (net (code "216") (name "Net-(BATT350-Pad+)") (class "Default")
      (node (ref "BATT350") (pin "+") (pinfunction "+_+") (pintype "bidirectional"))
      (node (ref "BATT351") (pin "-") (pinfunction "-_-") (pintype "bidirectional"))
    )
    (net (code "217") (name "Net-(BATT351-Pad+)") (class "Default")
      (node (ref "BATT351") (pin "+") (pinfunction "+_+") (pintype "bidirectional"))
      (node (ref "BATT352") (pin "-") (pinfunction "-_-") (pintype "bidirectional"))
    )
    (net (code "218") (name "Net-(BATT352-Pad+)") (class "Default")
      (node (ref "BATT352") (pin "+") (pinfunction "+_+") (pintype "bidirectional"))
      (node (ref "BATT353") (pin "-") (pinfunction "-_-") (pintype "bidirectional"))
    )
    (net (code "219") (name "Net-(BATT353-Pad+)") (class "Default")
      (node (ref "BATT353") (pin "+") (pinfunction "+_+") (pintype "bidirectional"))
      (node (ref "BATT354") (pin "-") (pinfunction "-_-") (pintype "bidirectional"))
    )
    (net (code "220") (name "Net-(BATT354-Pad+)") (class "Default")
      (node (ref "BATT354") (pin "+") (pinfunction "+_+") (pintype "bidirectional"))
      (node (ref "BATT355") (pin "-") (pinfunction "-_-") (pintype "bidirectional"))
    )
    (net (code "221") (name "Net-(BATT355-Pad+)") (class "Default")
      (node (ref "BATT355") (pin "+") (pinfunction "+_+") (pintype "bidirectional"))
      (node (ref "BATT356") (pin "-") (pinfunction "-_-") (pintype "bidirectional"))
    )
    (net (code "222") (name "Net-(BMS1-Pad-)") (class "Default")
      (node (ref "BMS1") (pin "-") (pinfunction "-_-") (pintype "passive"))
      (node (ref "JP11") (pin "1") (pinfunction "1_1") (pintype "passive"))
      (node (ref "JP11") (pin "2") (pinfunction "2_2") (pintype "passive"))
      (node (ref "JP11") (pin "3") (pinfunction "3_3") (pintype "passive"))
    )
    (net (code "223") (name "Net-(BMS2-+-Pad+@1)") (class "Default")
      (node (ref "BMS2") (pin "+@1") (pinfunction "+_+@1") (pintype "passive"))
      (node (ref "JP12") (pin "1") (pinfunction "1_1") (pintype "passive"))
      (node (ref "JP12") (pin "2") (pinfunction "2_2") (pintype "passive"))
      (node (ref "JP12") (pin "3") (pinfunction "3_3") (pintype "passive"))
    )
    (net (code "224") (name "Net-(BMS2-Pad-)") (class "Default")
      (node (ref "BMS2") (pin "-") (pinfunction "-_-") (pintype "passive"))
      (node (ref "JP3") (pin "1") (pinfunction "1_1") (pintype "passive"))
      (node (ref "JP3") (pin "2") (pinfunction "2_2") (pintype "passive"))
      (node (ref "JP3") (pin "3") (pinfunction "3_3") (pintype "passive"))
    )
    (net (code "225") (name "Net-(BMS3-Pad+)") (class "Default")
      (node (ref "BMS3") (pin "+") (pinfunction "+_+") (pintype "passive"))
      (node (ref "JP4") (pin "1") (pinfunction "1_1") (pintype "passive"))
      (node (ref "JP4") (pin "2") (pinfunction "2_2") (pintype "passive"))
      (node (ref "JP4") (pin "3") (pinfunction "3_3") (pintype "passive"))
    )
    (net (code "226") (name "Net-(BMS3-Pad-)") (class "Default")
      (node (ref "BMS3") (pin "-") (pinfunction "-_-") (pintype "passive"))
      (node (ref "JP5") (pin "1") (pinfunction "1_1") (pintype "passive"))
      (node (ref "JP5") (pin "2") (pinfunction "2_2") (pintype "passive"))
      (node (ref "JP5") (pin "3") (pinfunction "3_3") (pintype "passive"))
    )
    (net (code "227") (name "Net-(BMS4-Pad+)") (class "Default")
      (node (ref "BMS4") (pin "+") (pinfunction "+_+") (pintype "passive"))
      (node (ref "JP6") (pin "1") (pinfunction "1_1") (pintype "passive"))
      (node (ref "JP6") (pin "2") (pinfunction "2_2") (pintype "passive"))
      (node (ref "JP6") (pin "3") (pinfunction "3_3") (pintype "passive"))
    )
    (net (code "228") (name "Net-(BMS4-Pad-)") (class "Default")
      (node (ref "BMS4") (pin "-") (pinfunction "-_-") (pintype "passive"))
      (node (ref "JP8") (pin "1") (pinfunction "1_1") (pintype "passive"))
      (node (ref "JP8") (pin "2") (pinfunction "2_2") (pintype "passive"))
      (node (ref "JP8") (pin "3") (pinfunction "3_3") (pintype "passive"))
    )
    (net (code "229") (name "Net-(BMS5-Pad+)") (class "Default")
      (node (ref "BMS5") (pin "+") (pinfunction "+_+") (pintype "passive"))
      (node (ref "JP7") (pin "1") (pinfunction "1_1") (pintype "passive"))
      (node (ref "JP7") (pin "2") (pinfunction "2_2") (pintype "passive"))
      (node (ref "JP7") (pin "3") (pinfunction "3_3") (pintype "passive"))
    )
    (net (code "230") (name "Net-(BMS5-Pad-)") (class "Default")
      (node (ref "BMS5") (pin "-") (pinfunction "-_-") (pintype "passive"))
      (node (ref "JP9") (pin "1") (pinfunction "1_1") (pintype "passive"))
      (node (ref "JP9") (pin "2") (pinfunction "2_2") (pintype "passive"))
      (node (ref "JP9") (pin "3") (pinfunction "3_3") (pintype "passive"))
    )
    (net (code "231") (name "Net-(BMS6-Pad+)") (class "Default")
      (node (ref "BMS6") (pin "+") (pinfunction "+_+") (pintype "passive"))
      (node (ref "JP10") (pin "1") (pinfunction "1_1") (pintype "passive"))
      (node (ref "JP10") (pin "2") (pinfunction "2_2") (pintype "passive"))
      (node (ref "JP10") (pin "3") (pinfunction "3_3") (pintype "passive"))
    )
    (net (code "232") (name "Net-(DISCHARGE-Pad1)") (class "Default")
      (node (ref "DISCHARGE") (pin "1") (pinfunction "1_1") (pintype "passive"))
      (node (ref "R2") (pin "1") (pinfunction "1_1") (pintype "passive"))
    )
    (net (code "233") (name "Net-(F3-Pad1)") (class "Default")
      (node (ref "F3") (pin "1") (pinfunction "1_1") (pintype "passive"))
      (node (ref "K2") (pin "S") (pinfunction "S_S") (pintype "passive"))
    )
    (net (code "234") (name "Net-(F6-Pad2)") (class "Default")
      (node (ref "F6") (pin "2") (pinfunction "2_2") (pintype "passive"))
      (node (ref "R1") (pin "1") (pinfunction "1_1") (pintype "passive"))
    )
    (net (code "235") (name "Net-(JP1-1)") (class "Default")
      (node (ref "JP1") (pin "P$1") (pinfunction "1_P$1") (pintype "passive"))
      (node (ref "R1") (pin "2") (pinfunction "2_2") (pintype "passive"))
    )
    (net (code "236") (name "Net-(JP2-1)") (class "Default")
      (node (ref "JP2") (pin "P$1") (pinfunction "1_P$1") (pintype "passive"))
      (node (ref "R2") (pin "2") (pinfunction "2_2") (pintype "passive"))
    )
    (net (code "237") (name "Net-(K1B-P)") (class "Default")
      (node (ref "F1") (pin "1") (pinfunction "1_1") (pintype "passive"))
      (node (ref "K1") (pin "COM") (pinfunction "P_COM") (pintype "passive"))
    )
    (net (code "238") (name "Net-(K2-PadP)") (class "Default")
      (node (ref "K2") (pin "P") (pinfunction "P_P") (pintype "passive"))
      (node (ref "PRECHARGE") (pin "2") (pinfunction "2_2") (pintype "passive"))
    )
    (net (code "239") (name "Net-(K5B-O)") (class "Default")
      (node (ref "DISCHARGE") (pin "2") (pinfunction "2_2") (pintype "passive"))
      (node (ref "K5") (pin "NC") (pinfunction "O_NC") (pintype "passive"))
    )
    (net (code "240") (name "Net-(K5B-P)") (class "Default")
      (node (ref "F6") (pin "1") (pinfunction "1_1") (pintype "passive"))
      (node (ref "K5") (pin "COM") (pinfunction "P_COM") (pintype "passive"))
    )
    (net (code "241") (name "POS") (class "Default")
      (node (ref "F2") (pin "2") (pinfunction "2_2") (pintype "passive"))
      (node (ref "F4") (pin "2") (pinfunction "2_2") (pintype "passive"))
      (node (ref "F5") (pin "2") (pinfunction "2_2") (pintype "passive"))
    )
    (net (code "242") (name "PRE-CHARGE") (class "Default")
      (node (ref "K2") (pin "1") (pinfunction "1_1") (pintype "passive"))
      (node (ref "K3") (pin "1") (pinfunction "1_1") (pintype "passive"))
      (node (ref "K5") (pin "1") (pinfunction "1_1") (pintype "passive"))
    )
    (net (code "243") (name "TS+\\") (class "Default")
      (node (ref "F7") (pin "2") (pinfunction "2_2") (pintype "passive"))
      (node (ref "K1") (pin "NO") (pinfunction "S_NO") (pintype "passive"))
      (node (ref "PRECHARGE") (pin "1") (pinfunction "1_1") (pintype "passive"))
    )
    (net (code "244") (name "TS-") (class "Default")
      (node (ref "K3") (pin "NO") (pinfunction "S_NO") (pintype "passive"))
    )
    (net (code "245") (name "unconnected-(BMS1-+-Pad+@1)") (class "Default")
      (node (ref "BMS1") (pin "+@1") (pinfunction "+_+@1") (pintype "passive"))
    )
    (net (code "246") (name "unconnected-(BMS2-Pad+)") (class "Default")
      (node (ref "BMS2") (pin "+") (pinfunction "+_+") (pintype "passive"))
    )
    (net (code "247") (name "unconnected-(BMS3-+-Pad+@1)") (class "Default")
      (node (ref "BMS3") (pin "+@1") (pinfunction "+_+@1") (pintype "passive"))
    )
    (net (code "248") (name "unconnected-(BMS4-+-Pad+@1)") (class "Default")
      (node (ref "BMS4") (pin "+@1") (pinfunction "+_+@1") (pintype "passive"))
    )
    (net (code "249") (name "unconnected-(BMS5-+-Pad+@1)") (class "Default")
      (node (ref "BMS5") (pin "+@1") (pinfunction "+_+@1") (pintype "passive"))
    )
    (net (code "250") (name "unconnected-(BMS6-+-Pad+@1)") (class "Default")
      (node (ref "BMS6") (pin "+@1") (pinfunction "+_+@1") (pintype "passive"))
    )
    (net (code "251") (name "unconnected-(F7-Pad1)") (class "Default")
      (node (ref "F7") (pin "1") (pinfunction "1_1") (pintype "passive"))
    )
    (net (code "252") (name "unconnected-(K5B-S-PadNO)") (class "Default")
      (node (ref "K5") (pin "NO") (pinfunction "S_NO") (pintype "passive"))
    )
  )
)
